# PCB-CMB-6_SKAARDUINO.net
KiCad netlist of a schematic drawn in EAGLE
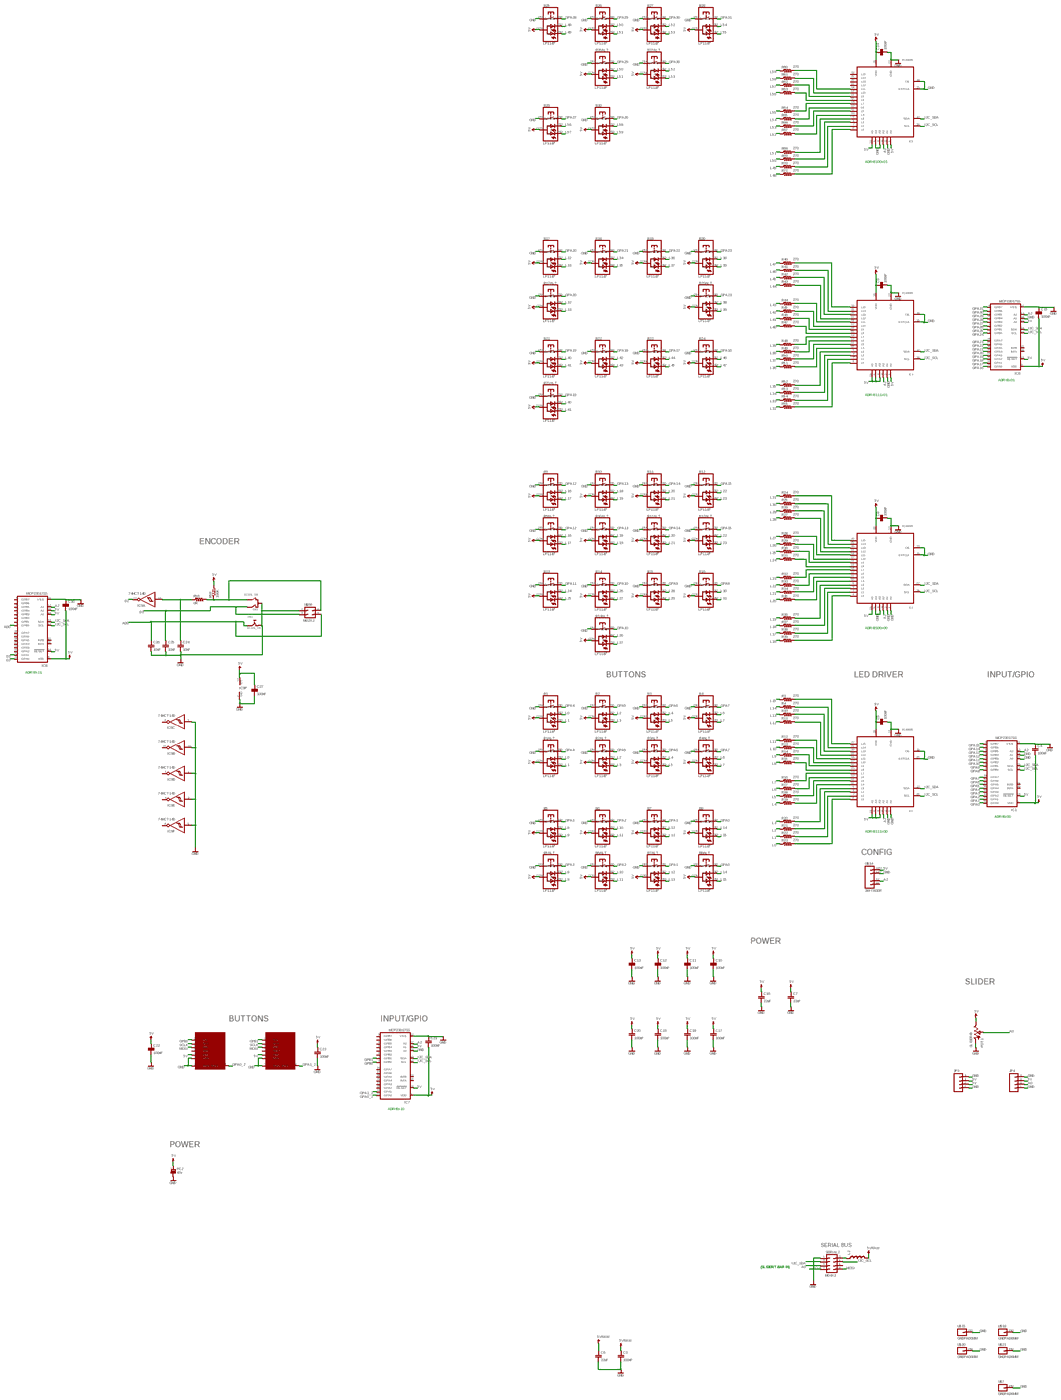
[diagram p0: schematic, sheet 1, overview]
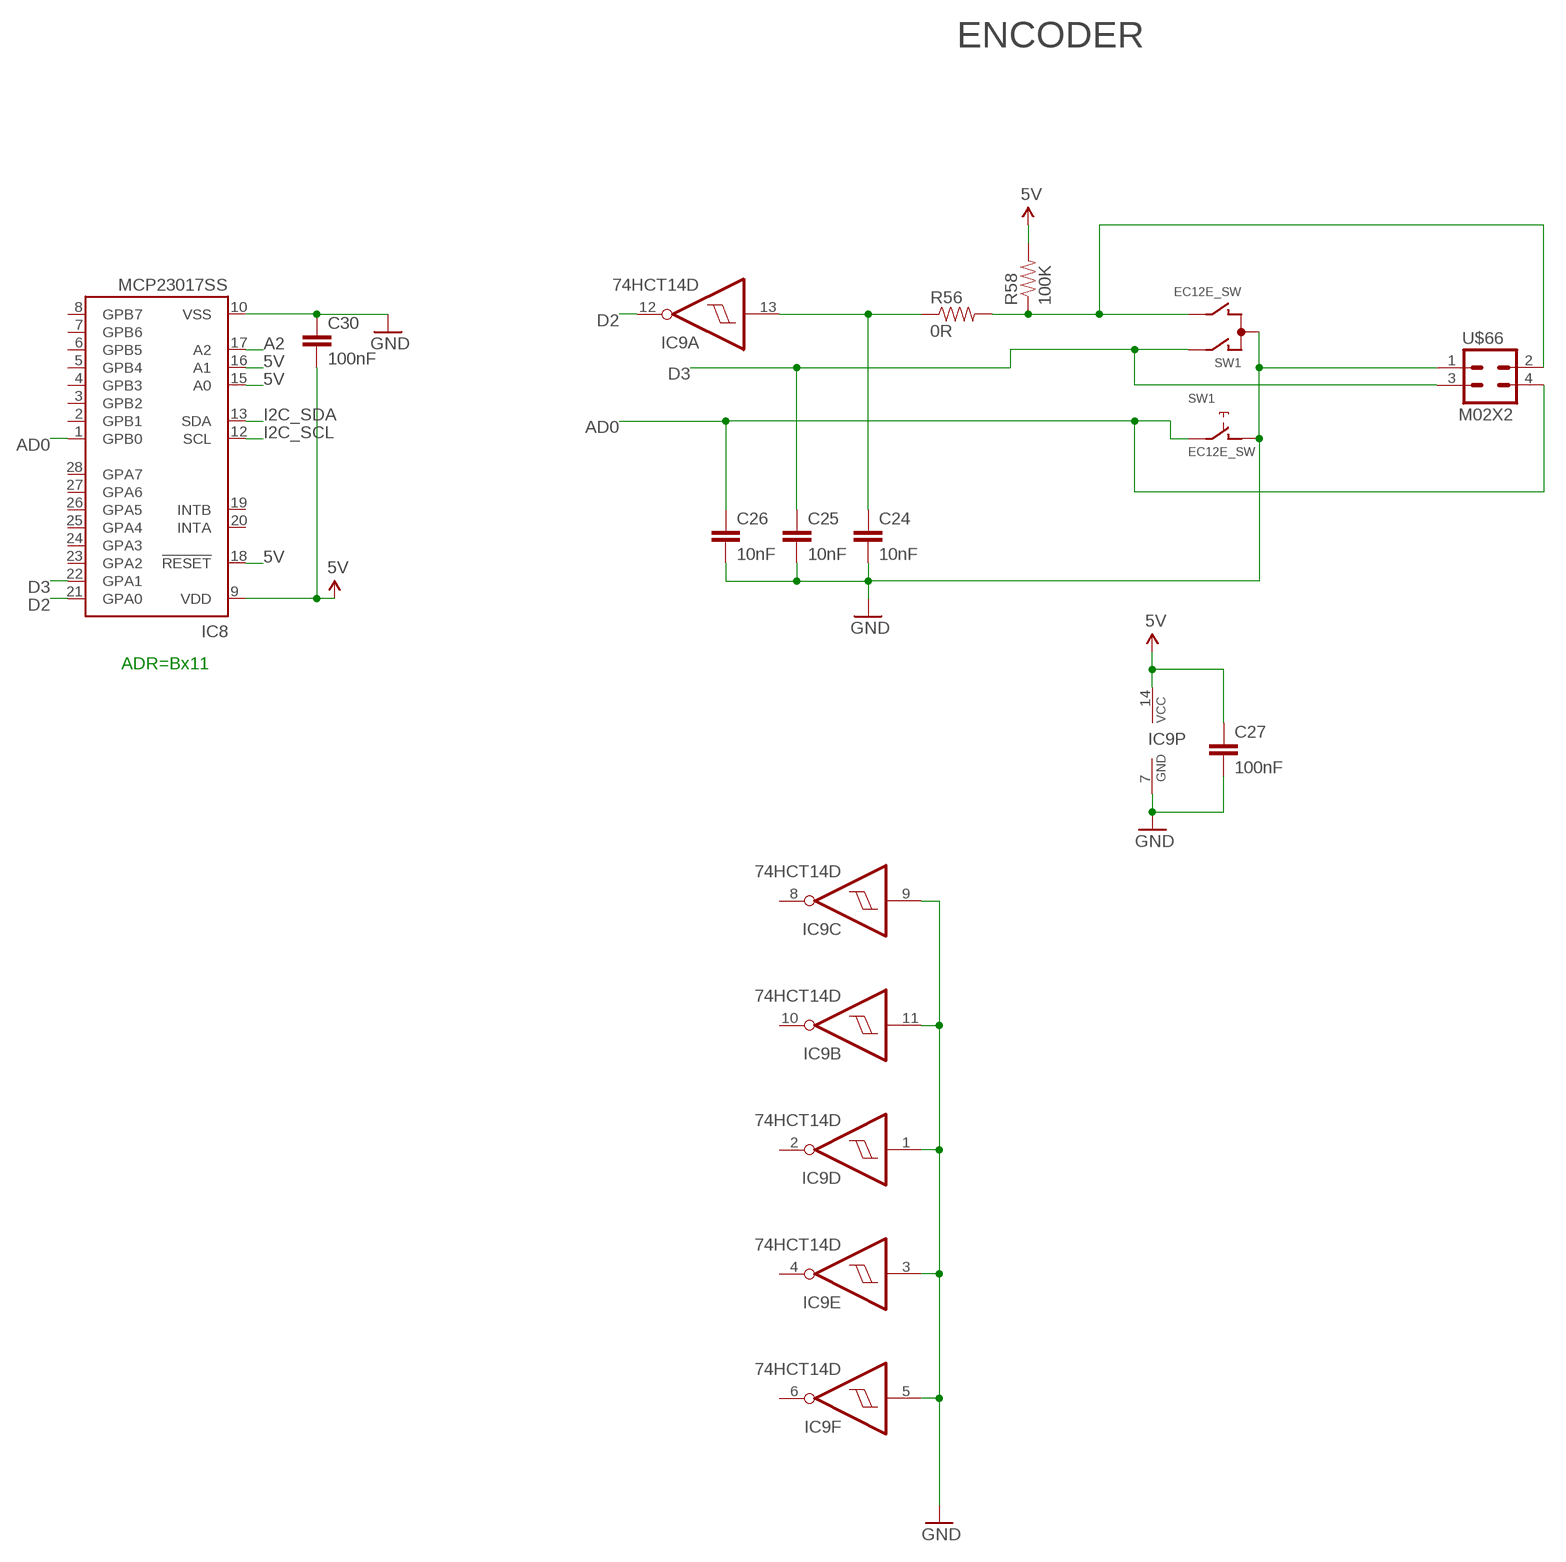
[diagram p1: schematic, sheet 1, part 1 of 5]
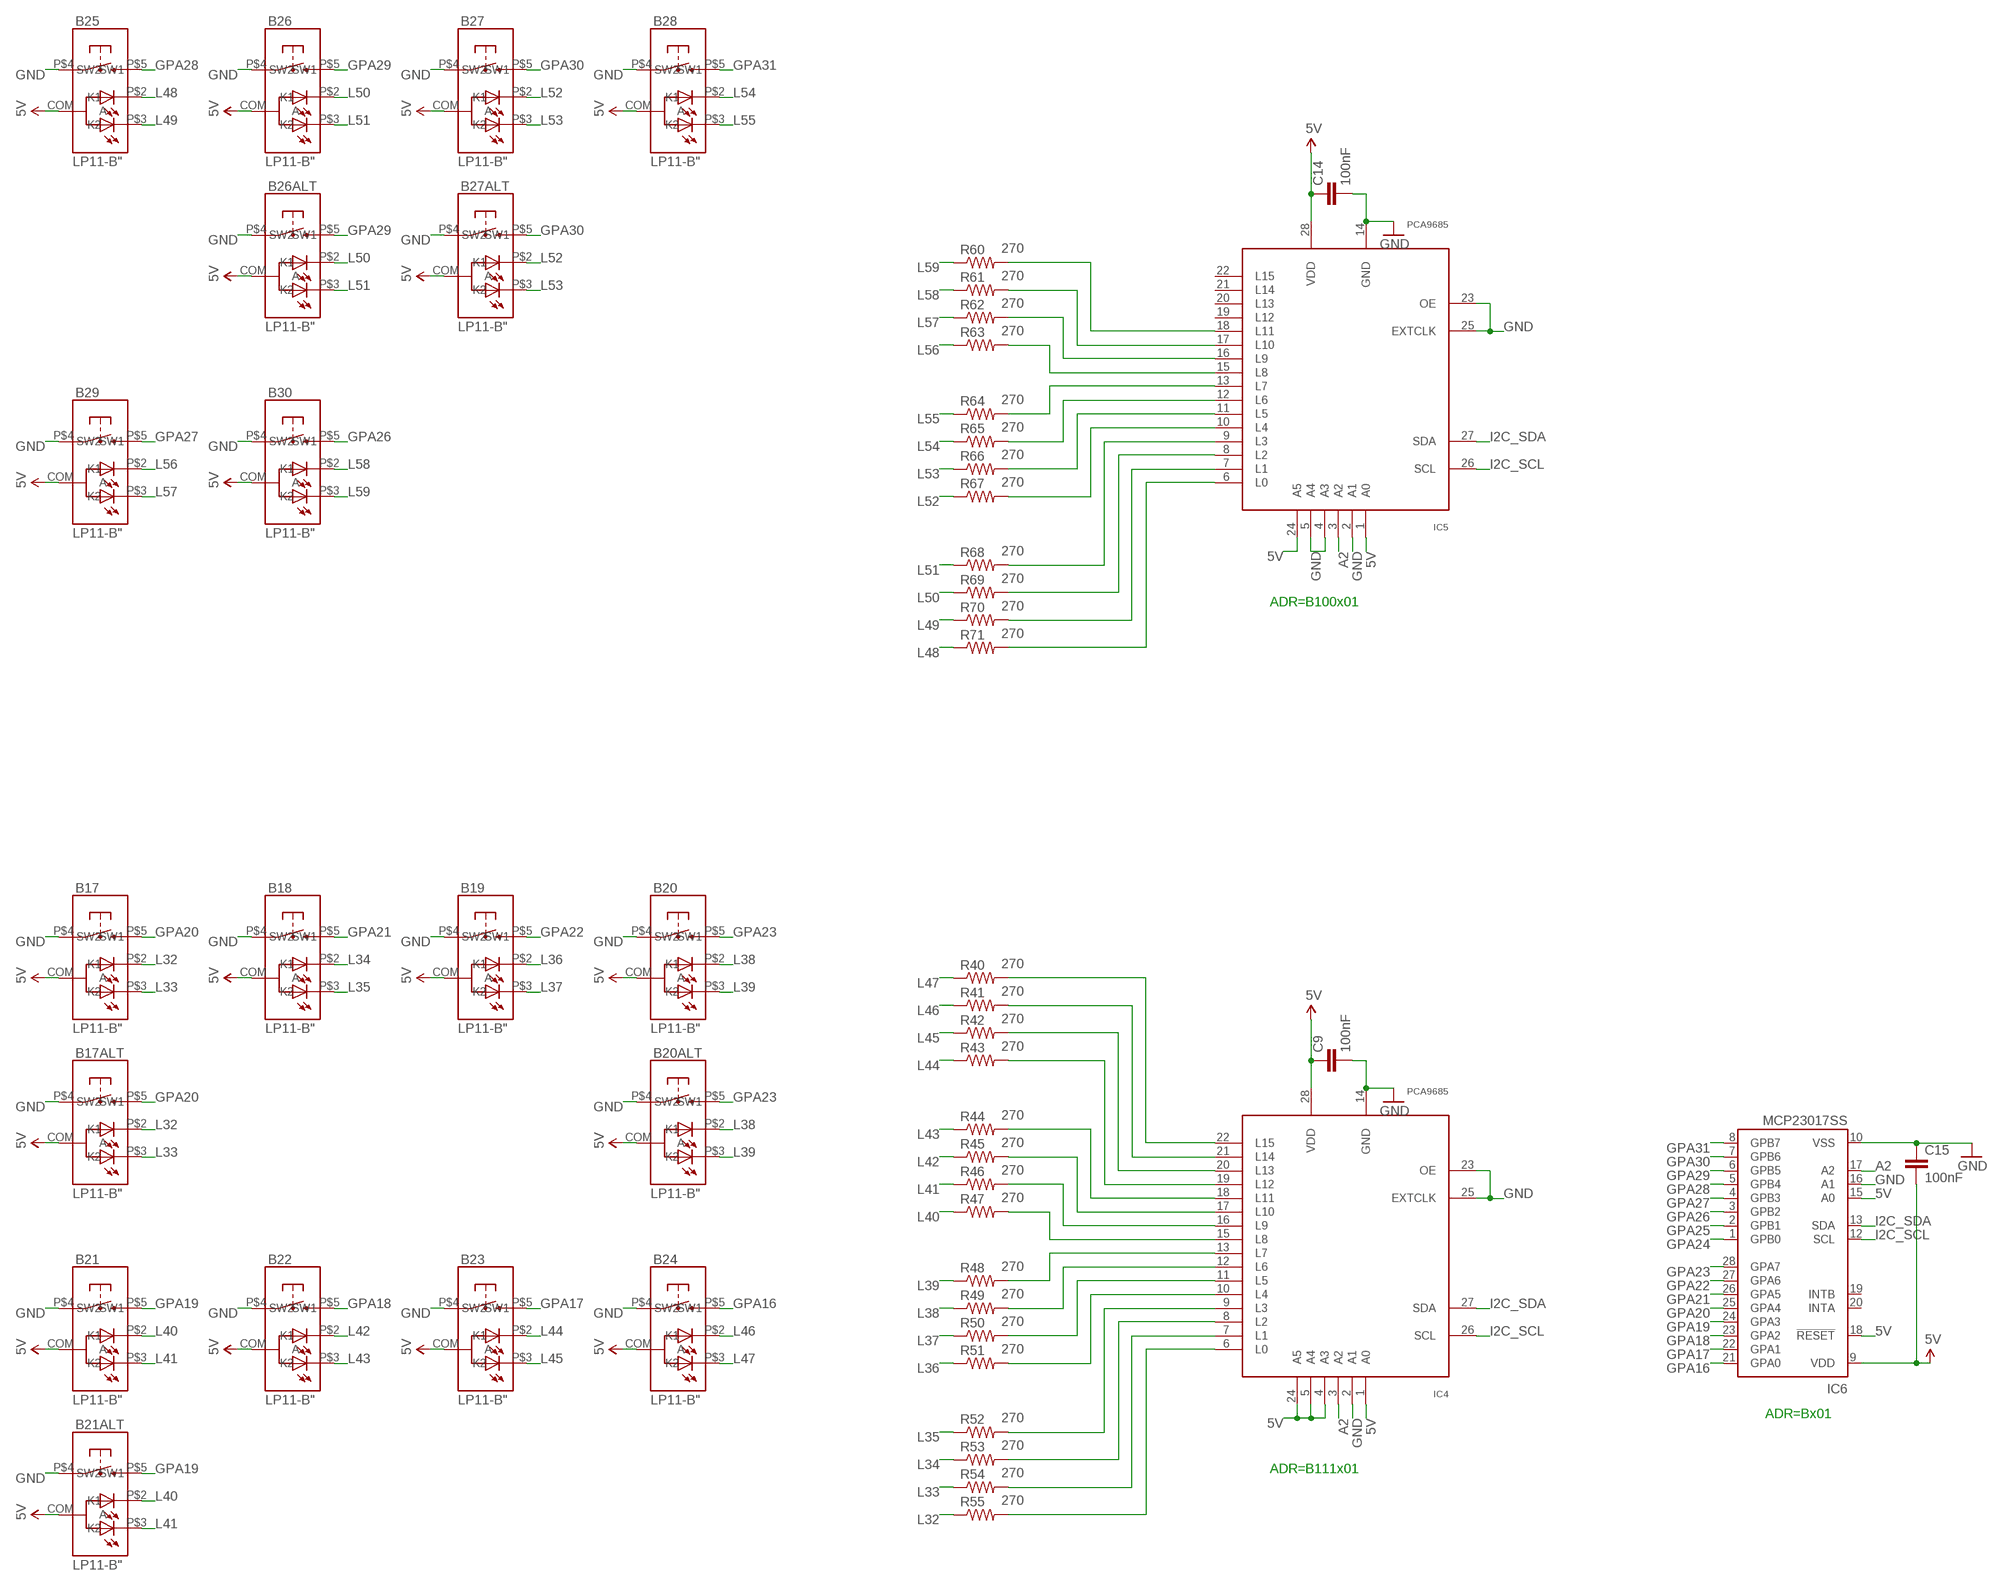
[diagram p2: schematic, sheet 1, part 2 of 5]
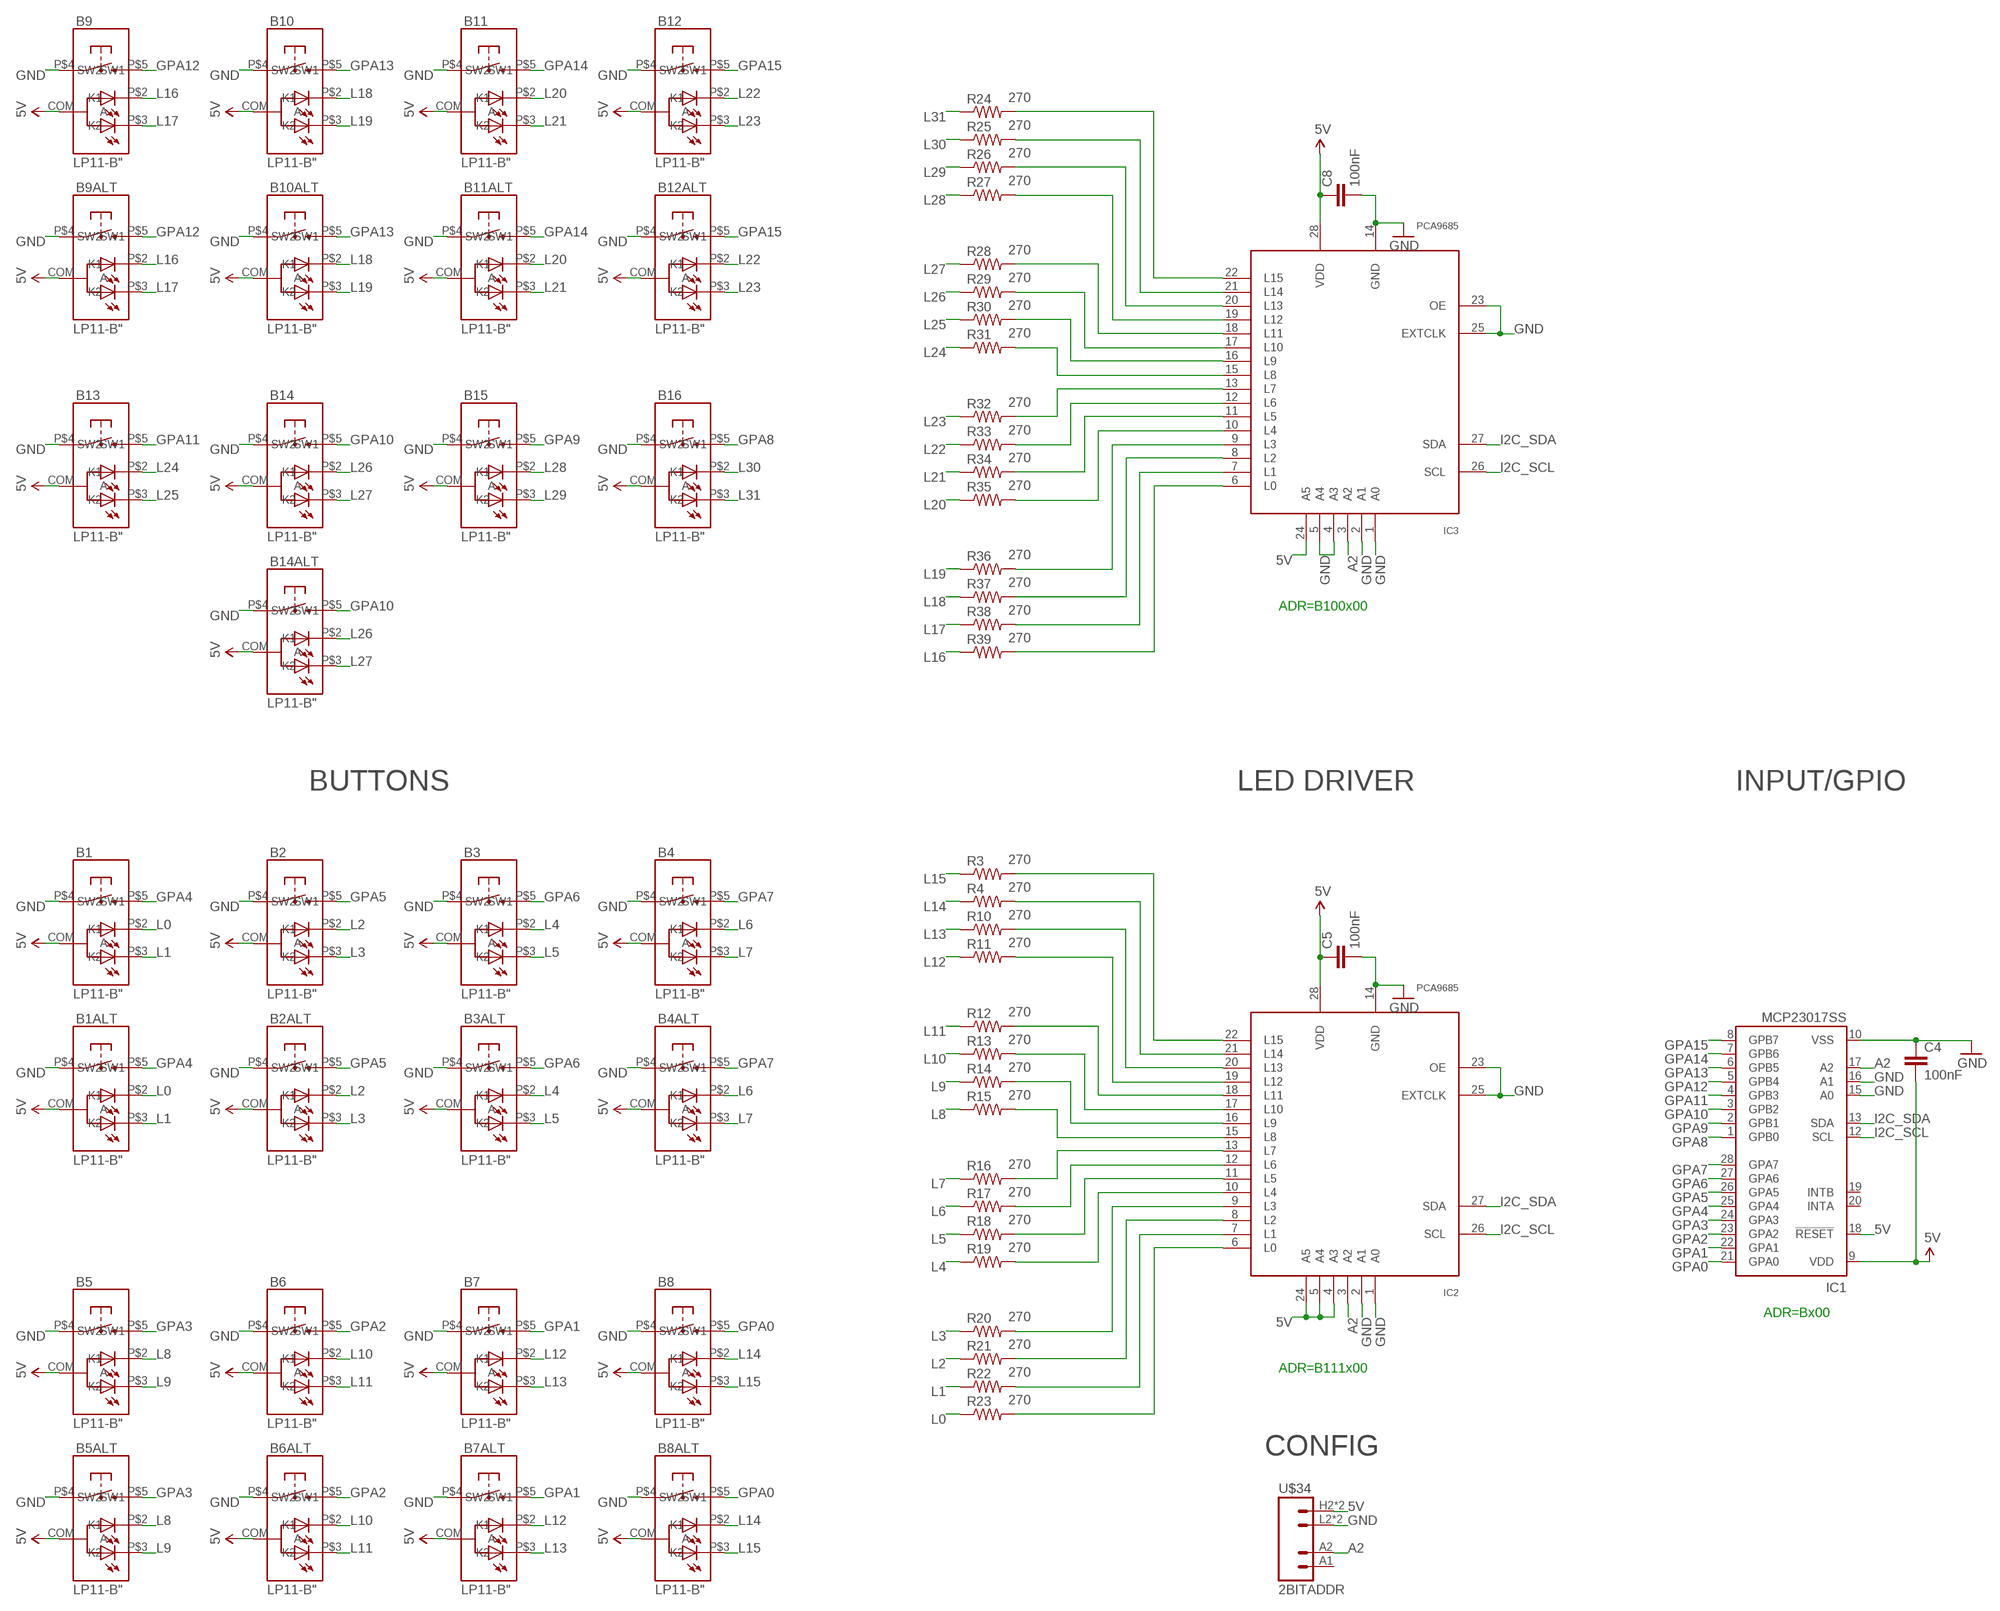
[diagram p3: schematic, sheet 1, part 3 of 5]
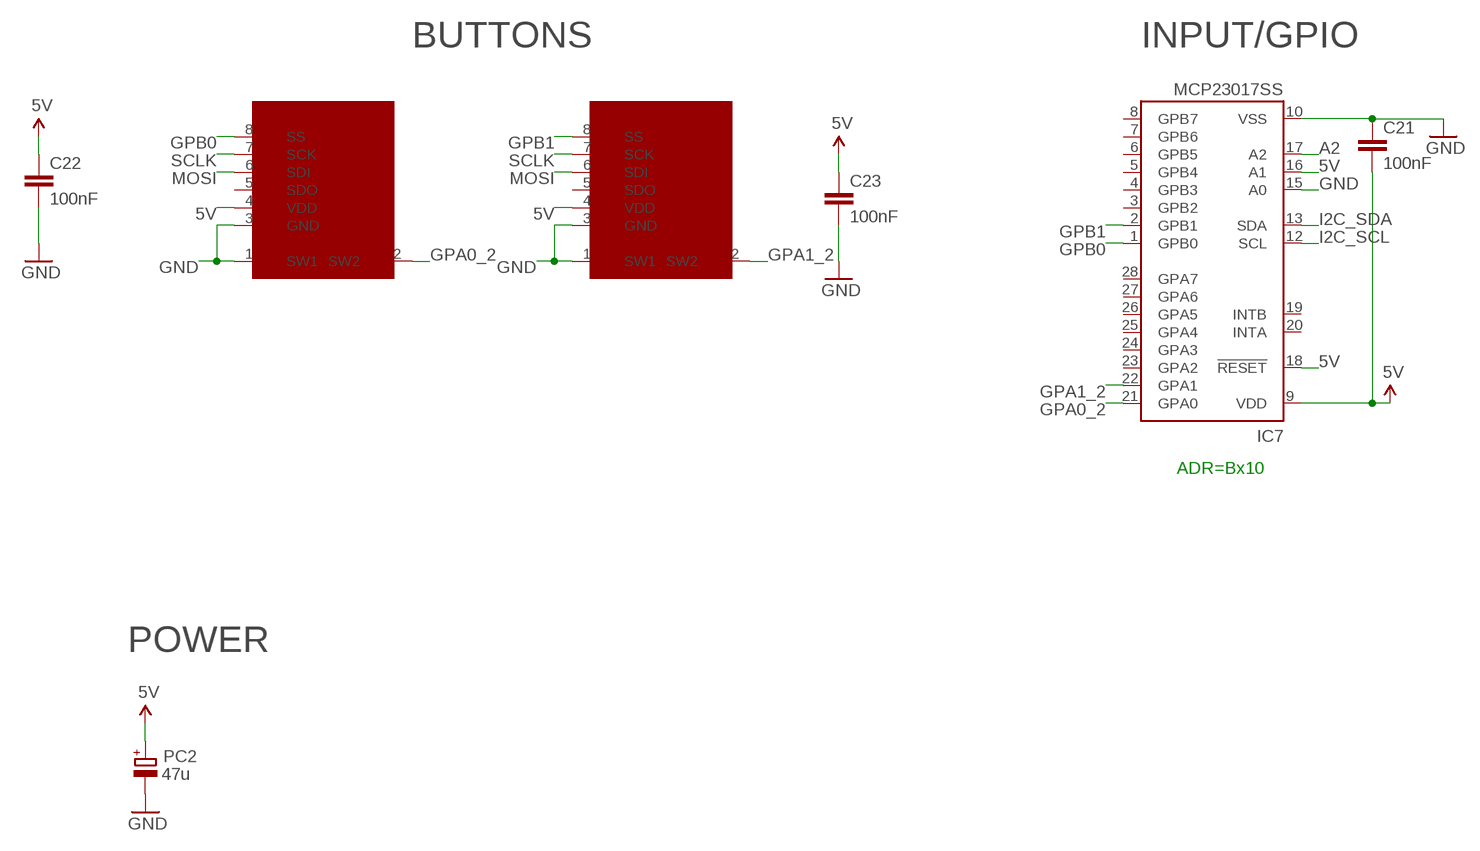
[diagram p4: schematic, sheet 1, part 4 of 5]
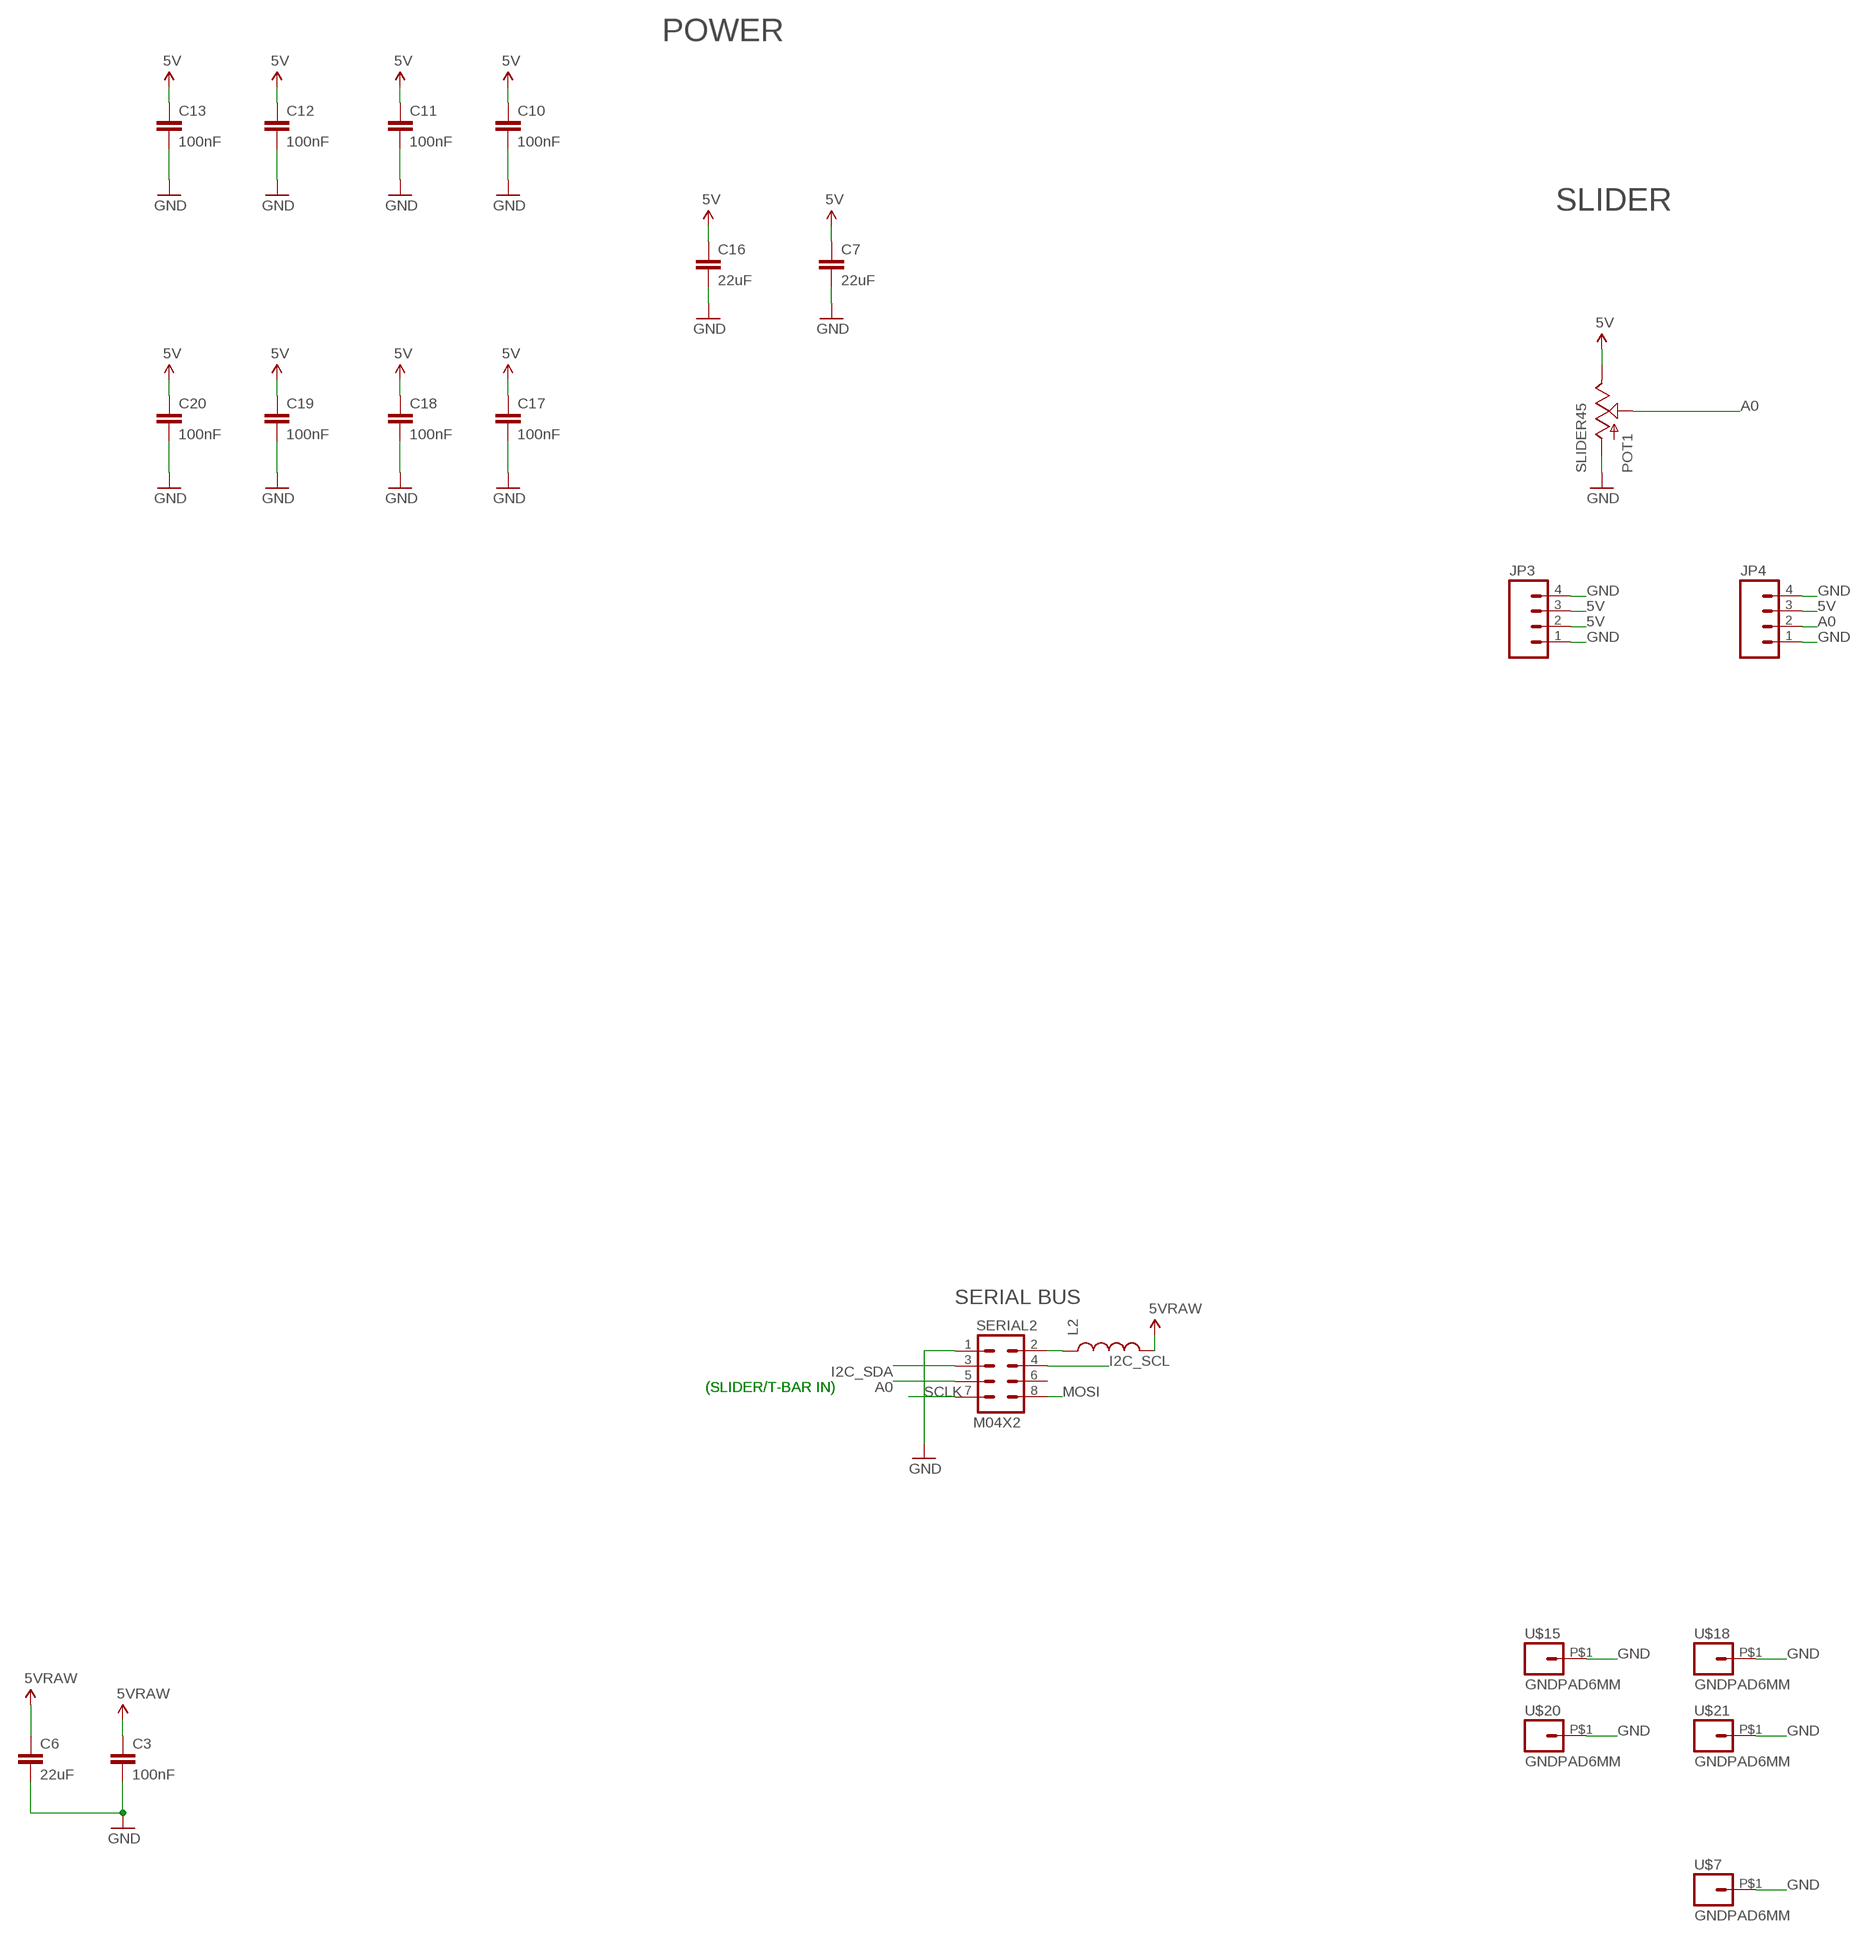
[diagram p5: schematic, sheet 1, part 5 of 5]

(export (version "E")
  (design (tool "Eeschema 10.0.6"))
  (components
    (comp (ref "B1")
      (value "LP11-B\"")
      (footprint "eagle-import:LP11")
      (libsource (lib "eagle-import") (part "LP11-B{dblquote}"))
    )
    (comp (ref "B1ALT")
      (value "LP11-B\"")
      (footprint "eagle-import:LP11")
      (libsource (lib "eagle-import") (part "LP11-B{dblquote}"))
    )
    (comp (ref "B2")
      (value "LP11-B\"")
      (footprint "eagle-import:LP11")
      (libsource (lib "eagle-import") (part "LP11-B{dblquote}"))
    )
    (comp (ref "B2ALT")
      (value "LP11-B\"")
      (footprint "eagle-import:LP11")
      (libsource (lib "eagle-import") (part "LP11-B{dblquote}"))
    )
    (comp (ref "B3")
      (value "LP11-B\"")
      (footprint "eagle-import:LP11")
      (libsource (lib "eagle-import") (part "LP11-B{dblquote}"))
    )
    (comp (ref "B3ALT")
      (value "LP11-B\"")
      (footprint "eagle-import:LP11")
      (libsource (lib "eagle-import") (part "LP11-B{dblquote}"))
    )
    (comp (ref "B4")
      (value "LP11-B\"")
      (footprint "eagle-import:LP11")
      (libsource (lib "eagle-import") (part "LP11-B{dblquote}"))
    )
    (comp (ref "B4ALT")
      (value "LP11-B\"")
      (footprint "eagle-import:LP11")
      (libsource (lib "eagle-import") (part "LP11-B{dblquote}"))
    )
    (comp (ref "B5")
      (value "LP11-B\"")
      (footprint "eagle-import:LP11")
      (libsource (lib "eagle-import") (part "LP11-B{dblquote}"))
    )
    (comp (ref "B5ALT")
      (value "LP11-B\"")
      (footprint "eagle-import:LP11")
      (libsource (lib "eagle-import") (part "LP11-B{dblquote}"))
    )
    (comp (ref "B6")
      (value "LP11-B\"")
      (footprint "eagle-import:LP11")
      (libsource (lib "eagle-import") (part "LP11-B{dblquote}"))
    )
    (comp (ref "B6ALT")
      (value "LP11-B\"")
      (footprint "eagle-import:LP11")
      (libsource (lib "eagle-import") (part "LP11-B{dblquote}"))
    )
    (comp (ref "B7")
      (value "LP11-B\"")
      (footprint "eagle-import:LP11")
      (libsource (lib "eagle-import") (part "LP11-B{dblquote}"))
    )
    (comp (ref "B7ALT")
      (value "LP11-B\"")
      (footprint "eagle-import:LP11")
      (libsource (lib "eagle-import") (part "LP11-B{dblquote}"))
    )
    (comp (ref "B8")
      (value "LP11-B\"")
      (footprint "eagle-import:LP11")
      (libsource (lib "eagle-import") (part "LP11-B{dblquote}"))
    )
    (comp (ref "B8ALT")
      (value "LP11-B\"")
      (footprint "eagle-import:LP11")
      (libsource (lib "eagle-import") (part "LP11-B{dblquote}"))
    )
    (comp (ref "B9")
      (value "LP11-B\"")
      (footprint "eagle-import:LP11")
      (libsource (lib "eagle-import") (part "LP11-B{dblquote}"))
    )
    (comp (ref "B9ALT")
      (value "LP11-B\"")
      (footprint "eagle-import:LP11")
      (libsource (lib "eagle-import") (part "LP11-B{dblquote}"))
    )
    (comp (ref "B10")
      (value "LP11-B\"")
      (footprint "eagle-import:LP11")
      (libsource (lib "eagle-import") (part "LP11-B{dblquote}"))
    )
    (comp (ref "B10ALT")
      (value "LP11-B\"")
      (footprint "eagle-import:LP11")
      (libsource (lib "eagle-import") (part "LP11-B{dblquote}"))
    )
    (comp (ref "B11")
      (value "LP11-B\"")
      (footprint "eagle-import:LP11")
      (libsource (lib "eagle-import") (part "LP11-B{dblquote}"))
    )
    (comp (ref "B11ALT")
      (value "LP11-B\"")
      (footprint "eagle-import:LP11")
      (libsource (lib "eagle-import") (part "LP11-B{dblquote}"))
    )
    (comp (ref "B12")
      (value "LP11-B\"")
      (footprint "eagle-import:LP11")
      (libsource (lib "eagle-import") (part "LP11-B{dblquote}"))
    )
    (comp (ref "B12ALT")
      (value "LP11-B\"")
      (footprint "eagle-import:LP11")
      (libsource (lib "eagle-import") (part "LP11-B{dblquote}"))
    )
    (comp (ref "B13")
      (value "LP11-B\"")
      (footprint "eagle-import:LP11")
      (libsource (lib "eagle-import") (part "LP11-B{dblquote}"))
    )
    (comp (ref "B14")
      (value "LP11-B\"")
      (footprint "eagle-import:LP11")
      (libsource (lib "eagle-import") (part "LP11-B{dblquote}"))
    )
    (comp (ref "B14ALT")
      (value "LP11-B\"")
      (footprint "eagle-import:LP11")
      (libsource (lib "eagle-import") (part "LP11-B{dblquote}"))
    )
    (comp (ref "B15")
      (value "LP11-B\"")
      (footprint "eagle-import:LP11")
      (libsource (lib "eagle-import") (part "LP11-B{dblquote}"))
    )
    (comp (ref "B16")
      (value "LP11-B\"")
      (footprint "eagle-import:LP11")
      (libsource (lib "eagle-import") (part "LP11-B{dblquote}"))
    )
    (comp (ref "B17")
      (value "LP11-B\"")
      (footprint "eagle-import:LP11")
      (libsource (lib "eagle-import") (part "LP11-B{dblquote}"))
    )
    (comp (ref "B17ALT")
      (value "LP11-B\"")
      (footprint "eagle-import:LP11")
      (libsource (lib "eagle-import") (part "LP11-B{dblquote}"))
    )
    (comp (ref "B18")
      (value "LP11-B\"")
      (footprint "eagle-import:LP11")
      (libsource (lib "eagle-import") (part "LP11-B{dblquote}"))
    )
    (comp (ref "B19")
      (value "LP11-B\"")
      (footprint "eagle-import:LP11")
      (libsource (lib "eagle-import") (part "LP11-B{dblquote}"))
    )
    (comp (ref "B20")
      (value "LP11-B\"")
      (footprint "eagle-import:LP11")
      (libsource (lib "eagle-import") (part "LP11-B{dblquote}"))
    )
    (comp (ref "B20ALT")
      (value "LP11-B\"")
      (footprint "eagle-import:LP11")
      (libsource (lib "eagle-import") (part "LP11-B{dblquote}"))
    )
    (comp (ref "B21")
      (value "LP11-B\"")
      (footprint "eagle-import:LP11")
      (libsource (lib "eagle-import") (part "LP11-B{dblquote}"))
    )
    (comp (ref "B21ALT")
      (value "LP11-B\"")
      (footprint "eagle-import:LP11")
      (libsource (lib "eagle-import") (part "LP11-B{dblquote}"))
    )
    (comp (ref "B22")
      (value "LP11-B\"")
      (footprint "eagle-import:LP11")
      (libsource (lib "eagle-import") (part "LP11-B{dblquote}"))
    )
    (comp (ref "B23")
      (value "LP11-B\"")
      (footprint "eagle-import:LP11")
      (libsource (lib "eagle-import") (part "LP11-B{dblquote}"))
    )
    (comp (ref "B24")
      (value "LP11-B\"")
      (footprint "eagle-import:LP11")
      (libsource (lib "eagle-import") (part "LP11-B{dblquote}"))
    )
    (comp (ref "B25")
      (value "LP11-B\"")
      (footprint "eagle-import:LP11")
      (libsource (lib "eagle-import") (part "LP11-B{dblquote}"))
    )
    (comp (ref "B26")
      (value "LP11-B\"")
      (footprint "eagle-import:LP11")
      (libsource (lib "eagle-import") (part "LP11-B{dblquote}"))
    )
    (comp (ref "B26ALT")
      (value "LP11-B\"")
      (footprint "eagle-import:LP11")
      (libsource (lib "eagle-import") (part "LP11-B{dblquote}"))
    )
    (comp (ref "B27")
      (value "LP11-B\"")
      (footprint "eagle-import:LP11")
      (libsource (lib "eagle-import") (part "LP11-B{dblquote}"))
    )
    (comp (ref "B27ALT")
      (value "LP11-B\"")
      (footprint "eagle-import:LP11")
      (libsource (lib "eagle-import") (part "LP11-B{dblquote}"))
    )
    (comp (ref "B28")
      (value "LP11-B\"")
      (footprint "eagle-import:LP11")
      (libsource (lib "eagle-import") (part "LP11-B{dblquote}"))
    )
    (comp (ref "B29")
      (value "LP11-B\"")
      (footprint "eagle-import:LP11")
      (libsource (lib "eagle-import") (part "LP11-B{dblquote}"))
    )
    (comp (ref "B30")
      (value "LP11-B\"")
      (footprint "eagle-import:LP11")
      (libsource (lib "eagle-import") (part "LP11-B{dblquote}"))
    )
    (comp (ref "C3")
      (value "100nF")
      (footprint "eagle-import:0603-CAP")
      (libsource (lib "eagle-import") (part "CAP0603-CAP"))
    )
    (comp (ref "C4")
      (value "100nF")
      (footprint "eagle-import:0603-CAP")
      (libsource (lib "eagle-import") (part "CAP0603-CAP"))
    )
    (comp (ref "C5")
      (value "100nF")
      (footprint "eagle-import:0603-CAP")
      (libsource (lib "eagle-import") (part "CAP0603-CAP"))
    )
    (comp (ref "C6")
      (value "22uF")
      (footprint "eagle-import:0805")
      (libsource (lib "eagle-import") (part "CAP0805"))
    )
    (comp (ref "C7")
      (value "22uF")
      (footprint "eagle-import:0805")
      (libsource (lib "eagle-import") (part "CAP0805"))
    )
    (comp (ref "C8")
      (value "100nF")
      (footprint "eagle-import:0603-CAP")
      (libsource (lib "eagle-import") (part "CAP0603-CAP"))
    )
    (comp (ref "C9")
      (value "100nF")
      (footprint "eagle-import:0603-CAP")
      (libsource (lib "eagle-import") (part "CAP0603-CAP"))
    )
    (comp (ref "C10")
      (value "100nF")
      (footprint "eagle-import:0603-CAP")
      (libsource (lib "eagle-import") (part "CAP0603-CAP"))
    )
    (comp (ref "C11")
      (value "100nF")
      (footprint "eagle-import:0603-CAP")
      (libsource (lib "eagle-import") (part "CAP0603-CAP"))
    )
    (comp (ref "C12")
      (value "100nF")
      (footprint "eagle-import:0603-CAP")
      (libsource (lib "eagle-import") (part "CAP0603-CAP"))
    )
    (comp (ref "C13")
      (value "100nF")
      (footprint "eagle-import:0603-CAP")
      (libsource (lib "eagle-import") (part "CAP0603-CAP"))
    )
    (comp (ref "C14")
      (value "100nF")
      (footprint "eagle-import:0603-CAP")
      (libsource (lib "eagle-import") (part "CAP0603-CAP"))
    )
    (comp (ref "C15")
      (value "100nF")
      (footprint "eagle-import:0603-CAP")
      (libsource (lib "eagle-import") (part "CAP0603-CAP"))
    )
    (comp (ref "C16")
      (value "22uF")
      (footprint "eagle-import:0805")
      (libsource (lib "eagle-import") (part "CAP0805"))
    )
    (comp (ref "C17")
      (value "100nF")
      (footprint "eagle-import:0603-CAP")
      (libsource (lib "eagle-import") (part "CAP0603-CAP"))
    )
    (comp (ref "C18")
      (value "100nF")
      (footprint "eagle-import:0603-CAP")
      (libsource (lib "eagle-import") (part "CAP0603-CAP"))
    )
    (comp (ref "C19")
      (value "100nF")
      (footprint "eagle-import:0603-CAP")
      (libsource (lib "eagle-import") (part "CAP0603-CAP"))
    )
    (comp (ref "C20")
      (value "100nF")
      (footprint "eagle-import:0603-CAP")
      (libsource (lib "eagle-import") (part "CAP0603-CAP"))
    )
    (comp (ref "C21")
      (value "100nF")
      (footprint "eagle-import:0603-CAP")
      (libsource (lib "eagle-import") (part "CAP0603-CAP"))
    )
    (comp (ref "C22")
      (value "100nF")
      (footprint "eagle-import:0603-CAP")
      (libsource (lib "eagle-import") (part "CAP0603-CAP"))
    )
    (comp (ref "C23")
      (value "100nF")
      (footprint "eagle-import:0603-CAP")
      (libsource (lib "eagle-import") (part "CAP0603-CAP"))
    )
    (comp (ref "C24")
      (value "10nF")
      (footprint "eagle-import:0603-CAP")
      (libsource (lib "eagle-import") (part "CAP0603-CAP"))
    )
    (comp (ref "C25")
      (value "10nF")
      (footprint "eagle-import:0603-CAP")
      (libsource (lib "eagle-import") (part "CAP0603-CAP"))
    )
    (comp (ref "C26")
      (value "10nF")
      (footprint "eagle-import:0603-CAP")
      (libsource (lib "eagle-import") (part "CAP0603-CAP"))
    )
    (comp (ref "C27")
      (value "100nF")
      (footprint "eagle-import:0603-CAP")
      (libsource (lib "eagle-import") (part "CAP0603-CAP"))
    )
    (comp (ref "C30")
      (value "100nF")
      (footprint "eagle-import:0603-CAP")
      (libsource (lib "eagle-import") (part "CAP0603-CAP"))
    )
    (comp (ref "IC1")
      (value "MCP23017SS")
      (footprint "eagle-import:SSOP28")
      (fields
        (field (name "MF") "MICROCHIP")
        (field (name "MPN") "MCP23017-E/SS")
        (field (name "MPN_1") "MCP23017-E/SS")
        (field (name "OC_FARNELL") "1467674")
        (field (name "OC_NEWARK") "31K2960")
      )
      (libsource (lib "eagle-import") (part "MCP23017SS"))
    )
    (comp (ref "IC2")
      (value "PCA9685")
      (footprint "eagle-import:TSSOP28")
      (libsource (lib "eagle-import") (part "PCA9685"))
    )
    (comp (ref "IC3")
      (value "PCA9685")
      (footprint "eagle-import:TSSOP28")
      (libsource (lib "eagle-import") (part "PCA9685"))
    )
    (comp (ref "IC4")
      (value "PCA9685")
      (footprint "eagle-import:TSSOP28")
      (libsource (lib "eagle-import") (part "PCA9685"))
    )
    (comp (ref "IC5")
      (value "PCA9685")
      (footprint "eagle-import:TSSOP28")
      (libsource (lib "eagle-import") (part "PCA9685"))
    )
    (comp (ref "IC6")
      (value "MCP23017SS")
      (footprint "eagle-import:SSOP28")
      (fields
        (field (name "MF") "MICROCHIP")
        (field (name "MPN") "MCP23017-E/SS")
        (field (name "MPN_1") "MCP23017-E/SS")
        (field (name "OC_FARNELL") "1467674")
        (field (name "OC_NEWARK") "31K2960")
      )
      (libsource (lib "eagle-import") (part "MCP23017SS"))
    )
    (comp (ref "IC7")
      (value "MCP23017SS")
      (footprint "eagle-import:SSOP28")
      (fields
        (field (name "MF") "MICROCHIP")
        (field (name "MPN") "MCP23017-E/SS")
        (field (name "MPN_1") "MCP23017-E/SS")
        (field (name "OC_FARNELL") "1467674")
        (field (name "OC_NEWARK") "31K2960")
      )
      (libsource (lib "eagle-import") (part "MCP23017SS"))
    )
    (comp (ref "IC8")
      (value "MCP23017SS")
      (footprint "eagle-import:SSOP28")
      (fields
        (field (name "MF") "MICROCHIP")
        (field (name "MPN") "MCP23017-E/SS")
        (field (name "MPN_1") "MCP23017-E/SS")
        (field (name "OC_FARNELL") "1467674")
        (field (name "OC_NEWARK") "31K2960")
      )
      (libsource (lib "eagle-import") (part "MCP23017SS"))
    )
    (comp (ref "IC9")
      (value "74HCT14D")
      (footprint "eagle-import:SO14")
      (libsource (lib "eagle-import") (part "7414DHCT"))
    )
    (comp (ref "JP3")
      (value "M04PTH")
      (footprint "eagle-import:1X04")
      (libsource (lib "eagle-import") (part "M04PTH"))
    )
    (comp (ref "JP4")
      (value "M04PTH")
      (footprint "eagle-import:1X04")
      (libsource (lib "eagle-import") (part "M04PTH"))
    )
    (comp (ref "L2")
      (value "INDUCTOR0805")
      (footprint "eagle-import:0805")
      (libsource (lib "eagle-import") (part "INDUCTOR0805"))
    )
    (comp (ref "PC2")
      (value "47u")
      (footprint "eagle-import:PANASONIC_D")
      (libsource (lib "eagle-import") (part "CPOL-EUD"))
    )
    (comp (ref "POT1")
      (value "SLIDER45")
      (footprint "eagle-import:SLIDER45")
      (libsource (lib "eagle-import") (part "SLIDER45"))
    )
    (comp (ref "R3")
      (value "270")
      (footprint "eagle-import:0603-RES")
      (libsource (lib "eagle-import") (part "RESISTOR0603-RES"))
    )
    (comp (ref "R4")
      (value "270")
      (footprint "eagle-import:0603-RES")
      (libsource (lib "eagle-import") (part "RESISTOR0603-RES"))
    )
    (comp (ref "R10")
      (value "270")
      (footprint "eagle-import:0603-RES")
      (libsource (lib "eagle-import") (part "RESISTOR0603-RES"))
    )
    (comp (ref "R11")
      (value "270")
      (footprint "eagle-import:0603-RES")
      (libsource (lib "eagle-import") (part "RESISTOR0603-RES"))
    )
    (comp (ref "R12")
      (value "270")
      (footprint "eagle-import:0603-RES")
      (libsource (lib "eagle-import") (part "RESISTOR0603-RES"))
    )
    (comp (ref "R13")
      (value "270")
      (footprint "eagle-import:0603-RES")
      (libsource (lib "eagle-import") (part "RESISTOR0603-RES"))
    )
    (comp (ref "R14")
      (value "270")
      (footprint "eagle-import:0603-RES")
      (libsource (lib "eagle-import") (part "RESISTOR0603-RES"))
    )
    (comp (ref "R15")
      (value "270")
      (footprint "eagle-import:0603-RES")
      (libsource (lib "eagle-import") (part "RESISTOR0603-RES"))
    )
    (comp (ref "R16")
      (value "270")
      (footprint "eagle-import:0603-RES")
      (libsource (lib "eagle-import") (part "RESISTOR0603-RES"))
    )
    (comp (ref "R17")
      (value "270")
      (footprint "eagle-import:0603-RES")
      (libsource (lib "eagle-import") (part "RESISTOR0603-RES"))
    )
    (comp (ref "R18")
      (value "270")
      (footprint "eagle-import:0603-RES")
      (libsource (lib "eagle-import") (part "RESISTOR0603-RES"))
    )
    (comp (ref "R19")
      (value "270")
      (footprint "eagle-import:0603-RES")
      (libsource (lib "eagle-import") (part "RESISTOR0603-RES"))
    )
    (comp (ref "R20")
      (value "270")
      (footprint "eagle-import:0603-RES")
      (libsource (lib "eagle-import") (part "RESISTOR0603-RES"))
    )
    (comp (ref "R21")
      (value "270")
      (footprint "eagle-import:0603-RES")
      (libsource (lib "eagle-import") (part "RESISTOR0603-RES"))
    )
    (comp (ref "R22")
      (value "270")
      (footprint "eagle-import:0603-RES")
      (libsource (lib "eagle-import") (part "RESISTOR0603-RES"))
    )
    (comp (ref "R23")
      (value "270")
      (footprint "eagle-import:0603-RES")
      (libsource (lib "eagle-import") (part "RESISTOR0603-RES"))
    )
    (comp (ref "R24")
      (value "270")
      (footprint "eagle-import:0603-RES")
      (libsource (lib "eagle-import") (part "RESISTOR0603-RES"))
    )
    (comp (ref "R25")
      (value "270")
      (footprint "eagle-import:0603-RES")
      (libsource (lib "eagle-import") (part "RESISTOR0603-RES"))
    )
    (comp (ref "R26")
      (value "270")
      (footprint "eagle-import:0603-RES")
      (libsource (lib "eagle-import") (part "RESISTOR0603-RES"))
    )
    (comp (ref "R27")
      (value "270")
      (footprint "eagle-import:0603-RES")
      (libsource (lib "eagle-import") (part "RESISTOR0603-RES"))
    )
    (comp (ref "R28")
      (value "270")
      (footprint "eagle-import:0603-RES")
      (libsource (lib "eagle-import") (part "RESISTOR0603-RES"))
    )
    (comp (ref "R29")
      (value "270")
      (footprint "eagle-import:0603-RES")
      (libsource (lib "eagle-import") (part "RESISTOR0603-RES"))
    )
    (comp (ref "R30")
      (value "270")
      (footprint "eagle-import:0603-RES")
      (libsource (lib "eagle-import") (part "RESISTOR0603-RES"))
    )
    (comp (ref "R31")
      (value "270")
      (footprint "eagle-import:0603-RES")
      (libsource (lib "eagle-import") (part "RESISTOR0603-RES"))
    )
    (comp (ref "R32")
      (value "270")
      (footprint "eagle-import:0603-RES")
      (libsource (lib "eagle-import") (part "RESISTOR0603-RES"))
    )
    (comp (ref "R33")
      (value "270")
      (footprint "eagle-import:0603-RES")
      (libsource (lib "eagle-import") (part "RESISTOR0603-RES"))
    )
    (comp (ref "R34")
      (value "270")
      (footprint "eagle-import:0603-RES")
      (libsource (lib "eagle-import") (part "RESISTOR0603-RES"))
    )
    (comp (ref "R35")
      (value "270")
      (footprint "eagle-import:0603-RES")
      (libsource (lib "eagle-import") (part "RESISTOR0603-RES"))
    )
    (comp (ref "R36")
      (value "270")
      (footprint "eagle-import:0603-RES")
      (libsource (lib "eagle-import") (part "RESISTOR0603-RES"))
    )
    (comp (ref "R37")
      (value "270")
      (footprint "eagle-import:0603-RES")
      (libsource (lib "eagle-import") (part "RESISTOR0603-RES"))
    )
    (comp (ref "R38")
      (value "270")
      (footprint "eagle-import:0603-RES")
      (libsource (lib "eagle-import") (part "RESISTOR0603-RES"))
    )
    (comp (ref "R39")
      (value "270")
      (footprint "eagle-import:0603-RES")
      (libsource (lib "eagle-import") (part "RESISTOR0603-RES"))
    )
    (comp (ref "R40")
      (value "270")
      (footprint "eagle-import:0603-RES")
      (libsource (lib "eagle-import") (part "RESISTOR0603-RES"))
    )
    (comp (ref "R41")
      (value "270")
      (footprint "eagle-import:0603-RES")
      (libsource (lib "eagle-import") (part "RESISTOR0603-RES"))
    )
    (comp (ref "R42")
      (value "270")
      (footprint "eagle-import:0603-RES")
      (libsource (lib "eagle-import") (part "RESISTOR0603-RES"))
    )
    (comp (ref "R43")
      (value "270")
      (footprint "eagle-import:0603-RES")
      (libsource (lib "eagle-import") (part "RESISTOR0603-RES"))
    )
    (comp (ref "R44")
      (value "270")
      (footprint "eagle-import:0603-RES")
      (libsource (lib "eagle-import") (part "RESISTOR0603-RES"))
    )
    (comp (ref "R45")
      (value "270")
      (footprint "eagle-import:0603-RES")
      (libsource (lib "eagle-import") (part "RESISTOR0603-RES"))
    )
    (comp (ref "R46")
      (value "270")
      (footprint "eagle-import:0603-RES")
      (libsource (lib "eagle-import") (part "RESISTOR0603-RES"))
    )
    (comp (ref "R47")
      (value "270")
      (footprint "eagle-import:0603-RES")
      (libsource (lib "eagle-import") (part "RESISTOR0603-RES"))
    )
    (comp (ref "R48")
      (value "270")
      (footprint "eagle-import:0603-RES")
      (libsource (lib "eagle-import") (part "RESISTOR0603-RES"))
    )
    (comp (ref "R49")
      (value "270")
      (footprint "eagle-import:0603-RES")
      (libsource (lib "eagle-import") (part "RESISTOR0603-RES"))
    )
    (comp (ref "R50")
      (value "270")
      (footprint "eagle-import:0603-RES")
      (libsource (lib "eagle-import") (part "RESISTOR0603-RES"))
    )
    (comp (ref "R51")
      (value "270")
      (footprint "eagle-import:0603-RES")
      (libsource (lib "eagle-import") (part "RESISTOR0603-RES"))
    )
    (comp (ref "R52")
      (value "270")
      (footprint "eagle-import:0603-RES")
      (libsource (lib "eagle-import") (part "RESISTOR0603-RES"))
    )
    (comp (ref "R53")
      (value "270")
      (footprint "eagle-import:0603-RES")
      (libsource (lib "eagle-import") (part "RESISTOR0603-RES"))
    )
    (comp (ref "R54")
      (value "270")
      (footprint "eagle-import:0603-RES")
      (libsource (lib "eagle-import") (part "RESISTOR0603-RES"))
    )
    (comp (ref "R55")
      (value "270")
      (footprint "eagle-import:0603-RES")
      (libsource (lib "eagle-import") (part "RESISTOR0603-RES"))
    )
    (comp (ref "R56")
      (value "0R")
      (footprint "eagle-import:0603-RES")
      (libsource (lib "eagle-import") (part "RESISTOR0603-RES"))
    )
    (comp (ref "R58")
      (value "100K")
      (footprint "eagle-import:0603-RES")
      (libsource (lib "eagle-import") (part "RESISTOR0603-RES"))
    )
    (comp (ref "R60")
      (value "270")
      (footprint "eagle-import:0603-RES")
      (libsource (lib "eagle-import") (part "RESISTOR0603-RES"))
    )
    (comp (ref "R61")
      (value "270")
      (footprint "eagle-import:0603-RES")
      (libsource (lib "eagle-import") (part "RESISTOR0603-RES"))
    )
    (comp (ref "R62")
      (value "270")
      (footprint "eagle-import:0603-RES")
      (libsource (lib "eagle-import") (part "RESISTOR0603-RES"))
    )
    (comp (ref "R63")
      (value "270")
      (footprint "eagle-import:0603-RES")
      (libsource (lib "eagle-import") (part "RESISTOR0603-RES"))
    )
    (comp (ref "R64")
      (value "270")
      (footprint "eagle-import:0603-RES")
      (libsource (lib "eagle-import") (part "RESISTOR0603-RES"))
    )
    (comp (ref "R65")
      (value "270")
      (footprint "eagle-import:0603-RES")
      (libsource (lib "eagle-import") (part "RESISTOR0603-RES"))
    )
    (comp (ref "R66")
      (value "270")
      (footprint "eagle-import:0603-RES")
      (libsource (lib "eagle-import") (part "RESISTOR0603-RES"))
    )
    (comp (ref "R67")
      (value "270")
      (footprint "eagle-import:0603-RES")
      (libsource (lib "eagle-import") (part "RESISTOR0603-RES"))
    )
    (comp (ref "R68")
      (value "270")
      (footprint "eagle-import:0603-RES")
      (libsource (lib "eagle-import") (part "RESISTOR0603-RES"))
    )
    (comp (ref "R69")
      (value "270")
      (footprint "eagle-import:0603-RES")
      (libsource (lib "eagle-import") (part "RESISTOR0603-RES"))
    )
    (comp (ref "R70")
      (value "270")
      (footprint "eagle-import:0603-RES")
      (libsource (lib "eagle-import") (part "RESISTOR0603-RES"))
    )
    (comp (ref "R71")
      (value "270")
      (footprint "eagle-import:0603-RES")
      (libsource (lib "eagle-import") (part "RESISTOR0603-RES"))
    )
    (comp (ref "SERIAL2")
      (value "M04X2")
      (footprint "eagle-import:2X4")
      (libsource (lib "eagle-import") (part "M04X2"))
    )
    (comp (ref "SSW1")
      (value "SMART_SWITCHSMART_SWITCH_8PIN")
      (footprint "eagle-import:SMART_SWITCH")
      (libsource (lib "eagle-import") (part "SMART_SWITCHSMART_SWITCH_8PIN"))
    )
    (comp (ref "SSW2")
      (value "SMART_SWITCHSMART_SWITCH_8PIN")
      (footprint "eagle-import:SMART_SWITCH")
      (libsource (lib "eagle-import") (part "SMART_SWITCHSMART_SWITCH_8PIN"))
    )
    (comp (ref "SW1")
      (value "EC12E_SW")
      (footprint "eagle-import:ALPS_EC12E_SW")
      (fields (field (name "MPN") "EC12E2424407"))
      (libsource (lib "eagle-import") (part "EC12E_SW"))
    )
    (comp (ref "U$7")
      (value "GNDPAD6MM")
      (footprint "eagle-import:3.2MMPAD6MM")
      (libsource (lib "eagle-import") (part "GNDPAD6MM"))
    )
    (comp (ref "U$15")
      (value "GNDPAD6MM")
      (footprint "eagle-import:3.2MMPAD6MM")
      (libsource (lib "eagle-import") (part "GNDPAD6MM"))
    )
    (comp (ref "U$18")
      (value "GNDPAD6MM")
      (footprint "eagle-import:3.2MMPAD6MM")
      (libsource (lib "eagle-import") (part "GNDPAD6MM"))
    )
    (comp (ref "U$20")
      (value "GNDPAD6MM")
      (footprint "eagle-import:3.2MMPAD6MM")
      (libsource (lib "eagle-import") (part "GNDPAD6MM"))
    )
    (comp (ref "U$21")
      (value "GNDPAD6MM")
      (footprint "eagle-import:3.2MMPAD6MM")
      (libsource (lib "eagle-import") (part "GNDPAD6MM"))
    )
    (comp (ref "U$34")
      (value "2BITADDR")
      (footprint "eagle-import:2BITADDR")
      (libsource (lib "eagle-import") (part "2BITADDR"))
    )
    (comp (ref "U$66")
      (value "M02X2")
      (footprint "eagle-import:2X2")
      (libsource (lib "eagle-import") (part "M02X2"))
    )
  )
  (nets
    (net (code "1") (name "5V") (class "Default")
      (node (ref "B1") (pin "COM") (pinfunction "A_COM") (pintype "bidirectional"))
      (node (ref "B10") (pin "COM") (pinfunction "A_COM") (pintype "bidirectional"))
      (node (ref "B10ALT") (pin "COM") (pinfunction "A_COM") (pintype "bidirectional"))
      (node (ref "B11") (pin "COM") (pinfunction "A_COM") (pintype "bidirectional"))
      (node (ref "B11ALT") (pin "COM") (pinfunction "A_COM") (pintype "bidirectional"))
      (node (ref "B12") (pin "COM") (pinfunction "A_COM") (pintype "bidirectional"))
      (node (ref "B12ALT") (pin "COM") (pinfunction "A_COM") (pintype "bidirectional"))
      (node (ref "B13") (pin "COM") (pinfunction "A_COM") (pintype "bidirectional"))
      (node (ref "B14") (pin "COM") (pinfunction "A_COM") (pintype "bidirectional"))
      (node (ref "B14ALT") (pin "COM") (pinfunction "A_COM") (pintype "bidirectional"))
      (node (ref "B15") (pin "COM") (pinfunction "A_COM") (pintype "bidirectional"))
      (node (ref "B16") (pin "COM") (pinfunction "A_COM") (pintype "bidirectional"))
      (node (ref "B17") (pin "COM") (pinfunction "A_COM") (pintype "bidirectional"))
      (node (ref "B17ALT") (pin "COM") (pinfunction "A_COM") (pintype "bidirectional"))
      (node (ref "B18") (pin "COM") (pinfunction "A_COM") (pintype "bidirectional"))
      (node (ref "B19") (pin "COM") (pinfunction "A_COM") (pintype "bidirectional"))
      (node (ref "B1ALT") (pin "COM") (pinfunction "A_COM") (pintype "bidirectional"))
      (node (ref "B2") (pin "COM") (pinfunction "A_COM") (pintype "bidirectional"))
      (node (ref "B20") (pin "COM") (pinfunction "A_COM") (pintype "bidirectional"))
      (node (ref "B20ALT") (pin "COM") (pinfunction "A_COM") (pintype "bidirectional"))
      (node (ref "B21") (pin "COM") (pinfunction "A_COM") (pintype "bidirectional"))
      (node (ref "B21ALT") (pin "COM") (pinfunction "A_COM") (pintype "bidirectional"))
      (node (ref "B22") (pin "COM") (pinfunction "A_COM") (pintype "bidirectional"))
      (node (ref "B23") (pin "COM") (pinfunction "A_COM") (pintype "bidirectional"))
      (node (ref "B24") (pin "COM") (pinfunction "A_COM") (pintype "bidirectional"))
      (node (ref "B25") (pin "COM") (pinfunction "A_COM") (pintype "bidirectional"))
      (node (ref "B26") (pin "COM") (pinfunction "A_COM") (pintype "bidirectional"))
      (node (ref "B26ALT") (pin "COM") (pinfunction "A_COM") (pintype "bidirectional"))
      (node (ref "B27") (pin "COM") (pinfunction "A_COM") (pintype "bidirectional"))
      (node (ref "B27ALT") (pin "COM") (pinfunction "A_COM") (pintype "bidirectional"))
      (node (ref "B28") (pin "COM") (pinfunction "A_COM") (pintype "bidirectional"))
      (node (ref "B29") (pin "COM") (pinfunction "A_COM") (pintype "bidirectional"))
      (node (ref "B2ALT") (pin "COM") (pinfunction "A_COM") (pintype "bidirectional"))
      (node (ref "B3") (pin "COM") (pinfunction "A_COM") (pintype "bidirectional"))
      (node (ref "B30") (pin "COM") (pinfunction "A_COM") (pintype "bidirectional"))
      (node (ref "B3ALT") (pin "COM") (pinfunction "A_COM") (pintype "bidirectional"))
      (node (ref "B4") (pin "COM") (pinfunction "A_COM") (pintype "bidirectional"))
      (node (ref "B4ALT") (pin "COM") (pinfunction "A_COM") (pintype "bidirectional"))
      (node (ref "B5") (pin "COM") (pinfunction "A_COM") (pintype "bidirectional"))
      (node (ref "B5ALT") (pin "COM") (pinfunction "A_COM") (pintype "bidirectional"))
      (node (ref "B6") (pin "COM") (pinfunction "A_COM") (pintype "bidirectional"))
      (node (ref "B6ALT") (pin "COM") (pinfunction "A_COM") (pintype "bidirectional"))
      (node (ref "B7") (pin "COM") (pinfunction "A_COM") (pintype "bidirectional"))
      (node (ref "B7ALT") (pin "COM") (pinfunction "A_COM") (pintype "bidirectional"))
      (node (ref "B8") (pin "COM") (pinfunction "A_COM") (pintype "bidirectional"))
      (node (ref "B8ALT") (pin "COM") (pinfunction "A_COM") (pintype "bidirectional"))
      (node (ref "B9") (pin "COM") (pinfunction "A_COM") (pintype "bidirectional"))
      (node (ref "B9ALT") (pin "COM") (pinfunction "A_COM") (pintype "bidirectional"))
      (node (ref "C10") (pin "1") (pinfunction "1_1") (pintype "passive"))
      (node (ref "C11") (pin "1") (pinfunction "1_1") (pintype "passive"))
      (node (ref "C12") (pin "1") (pinfunction "1_1") (pintype "passive"))
      (node (ref "C13") (pin "1") (pinfunction "1_1") (pintype "passive"))
      (node (ref "C14") (pin "1") (pinfunction "1_1") (pintype "passive"))
      (node (ref "C15") (pin "2") (pinfunction "2_2") (pintype "passive"))
      (node (ref "C16") (pin "1") (pinfunction "1_1") (pintype "passive"))
      (node (ref "C17") (pin "1") (pinfunction "1_1") (pintype "passive"))
      (node (ref "C18") (pin "1") (pinfunction "1_1") (pintype "passive"))
      (node (ref "C19") (pin "1") (pinfunction "1_1") (pintype "passive"))
      (node (ref "C20") (pin "1") (pinfunction "1_1") (pintype "passive"))
      (node (ref "C21") (pin "2") (pinfunction "2_2") (pintype "passive"))
      (node (ref "C22") (pin "1") (pinfunction "1_1") (pintype "passive"))
      (node (ref "C23") (pin "1") (pinfunction "1_1") (pintype "passive"))
      (node (ref "C27") (pin "1") (pinfunction "1_1") (pintype "passive"))
      (node (ref "C30") (pin "2") (pinfunction "2_2") (pintype "passive"))
      (node (ref "C4") (pin "2") (pinfunction "2_2") (pintype "passive"))
      (node (ref "C5") (pin "1") (pinfunction "1_1") (pintype "passive"))
      (node (ref "C7") (pin "1") (pinfunction "1_1") (pintype "passive"))
      (node (ref "C8") (pin "1") (pinfunction "1_1") (pintype "passive"))
      (node (ref "C9") (pin "1") (pinfunction "1_1") (pintype "passive"))
      (node (ref "IC1") (pin "18") (pinfunction "~{RESET}_18") (pintype "input"))
      (node (ref "IC1") (pin "9") (pinfunction "VDD_9") (pintype "power_in"))
      (node (ref "IC2") (pin "24") (pinfunction "A5_24") (pintype "input"))
      (node (ref "IC2") (pin "28") (pinfunction "VDD_28") (pintype "power_in"))
      (node (ref "IC2") (pin "4") (pinfunction "A3_4") (pintype "input"))
      (node (ref "IC2") (pin "5") (pinfunction "A4_5") (pintype "input"))
      (node (ref "IC3") (pin "24") (pinfunction "A5_24") (pintype "input"))
      (node (ref "IC3") (pin "28") (pinfunction "VDD_28") (pintype "power_in"))
      (node (ref "IC4") (pin "1") (pinfunction "A0_1") (pintype "input"))
      (node (ref "IC4") (pin "24") (pinfunction "A5_24") (pintype "input"))
      (node (ref "IC4") (pin "28") (pinfunction "VDD_28") (pintype "power_in"))
      (node (ref "IC4") (pin "4") (pinfunction "A3_4") (pintype "input"))
      (node (ref "IC4") (pin "5") (pinfunction "A4_5") (pintype "input"))
      (node (ref "IC5") (pin "1") (pinfunction "A0_1") (pintype "input"))
      (node (ref "IC5") (pin "24") (pinfunction "A5_24") (pintype "input"))
      (node (ref "IC5") (pin "28") (pinfunction "VDD_28") (pintype "power_in"))
      (node (ref "IC6") (pin "15") (pinfunction "A0_15") (pintype "input"))
      (node (ref "IC6") (pin "18") (pinfunction "~{RESET}_18") (pintype "input"))
      (node (ref "IC6") (pin "9") (pinfunction "VDD_9") (pintype "power_in"))
      (node (ref "IC7") (pin "16") (pinfunction "A1_16") (pintype "input"))
      (node (ref "IC7") (pin "18") (pinfunction "~{RESET}_18") (pintype "input"))
      (node (ref "IC7") (pin "9") (pinfunction "VDD_9") (pintype "power_in"))
      (node (ref "IC8") (pin "15") (pinfunction "A0_15") (pintype "input"))
      (node (ref "IC8") (pin "16") (pinfunction "A1_16") (pintype "input"))
      (node (ref "IC8") (pin "18") (pinfunction "~{RESET}_18") (pintype "input"))
      (node (ref "IC8") (pin "9") (pinfunction "VDD_9") (pintype "power_in"))
      (node (ref "IC9") (pin "14") (pinfunction "VCC_14") (pintype "power_in"))
      (node (ref "JP3") (pin "2") (pinfunction "2_2") (pintype "passive"))
      (node (ref "JP3") (pin "3") (pinfunction "3_3") (pintype "passive"))
      (node (ref "JP4") (pin "3") (pinfunction "3_3") (pintype "passive"))
      (node (ref "PC2") (pin "+") (pinfunction "+_+") (pintype "passive"))
      (node (ref "POT1") (pin "1") (pinfunction "E_1") (pintype "passive"))
      (node (ref "R58") (pin "2") (pinfunction "2_2") (pintype "passive"))
      (node (ref "SSW1") (pin "4") (pinfunction "VDD_4") (pintype "bidirectional"))
      (node (ref "SSW2") (pin "4") (pinfunction "VDD_4") (pintype "bidirectional"))
      (node (ref "U$34") (pin "H2") (pinfunction "VCC_H2") (pintype "passive"))
      (node (ref "U$34") (pin "H3") (pinfunction "VCC_H3") (pintype "passive"))
    )
    (net (code "2") (name "5V_RAW") (class "Default")
      (node (ref "C3") (pin "1") (pinfunction "1_1") (pintype "passive"))
      (node (ref "C6") (pin "1") (pinfunction "1_1") (pintype "passive"))
      (node (ref "L2") (pin "2") (pinfunction "2_2") (pintype "passive"))
    )
    (net (code "3") (name "A0") (class "Default")
      (node (ref "JP4") (pin "2") (pinfunction "2_2") (pintype "passive"))
      (node (ref "POT1") (pin "2A") (pinfunction "S_2A") (pintype "passive"))
      (node (ref "SERIAL2") (pin "5") (pinfunction "5_5") (pintype "passive"))
    )
    (net (code "4") (name "A2") (class "Default")
      (node (ref "IC1") (pin "17") (pinfunction "A2_17") (pintype "input"))
      (node (ref "IC2") (pin "3") (pinfunction "A2_3") (pintype "input"))
      (node (ref "IC3") (pin "3") (pinfunction "A2_3") (pintype "input"))
      (node (ref "IC4") (pin "3") (pinfunction "A2_3") (pintype "input"))
      (node (ref "IC5") (pin "3") (pinfunction "A2_3") (pintype "input"))
      (node (ref "IC6") (pin "17") (pinfunction "A2_17") (pintype "input"))
      (node (ref "IC7") (pin "17") (pinfunction "A2_17") (pintype "input"))
      (node (ref "IC8") (pin "17") (pinfunction "A2_17") (pintype "input"))
      (node (ref "U$34") (pin "A2") (pinfunction "A2_A2") (pintype "passive"))
    )
    (net (code "5") (name "AD0") (class "Default")
      (node (ref "C26") (pin "1") (pinfunction "1_1") (pintype "passive"))
      (node (ref "IC8") (pin "1") (pinfunction "GPB0_1") (pintype "bidirectional"))
      (node (ref "SW1") (pin "E") (pinfunction "2_E") (pintype "passive"))
      (node (ref "U$66") (pin "4") (pinfunction "4_4") (pintype "passive"))
    )
    (net (code "6") (name "D2") (class "Default")
      (node (ref "IC8") (pin "21") (pinfunction "GPA0_21") (pintype "bidirectional"))
      (node (ref "IC9") (pin "12") (pinfunction "O_12") (pintype "output"))
    )
    (net (code "7") (name "D3") (class "Default")
      (node (ref "C25") (pin "1") (pinfunction "1_1") (pintype "passive"))
      (node (ref "IC8") (pin "22") (pinfunction "GPA1_22") (pintype "bidirectional"))
      (node (ref "SW1") (pin "A") (pinfunction "A_A") (pintype "passive"))
      (node (ref "U$66") (pin "3") (pinfunction "3_3") (pintype "passive"))
    )
    (net (code "8") (name "GND") (class "Default")
      (node (ref "B1") (pin "P$4") (pinfunction "SW1_P$4") (pintype "bidirectional"))
      (node (ref "B10") (pin "P$4") (pinfunction "SW1_P$4") (pintype "bidirectional"))
      (node (ref "B10ALT") (pin "P$4") (pinfunction "SW1_P$4") (pintype "bidirectional"))
      (node (ref "B11") (pin "P$4") (pinfunction "SW1_P$4") (pintype "bidirectional"))
      (node (ref "B11ALT") (pin "P$4") (pinfunction "SW1_P$4") (pintype "bidirectional"))
      (node (ref "B12") (pin "P$4") (pinfunction "SW1_P$4") (pintype "bidirectional"))
      (node (ref "B12ALT") (pin "P$4") (pinfunction "SW1_P$4") (pintype "bidirectional"))
      (node (ref "B13") (pin "P$4") (pinfunction "SW1_P$4") (pintype "bidirectional"))
      (node (ref "B14") (pin "P$4") (pinfunction "SW1_P$4") (pintype "bidirectional"))
      (node (ref "B14ALT") (pin "P$4") (pinfunction "SW1_P$4") (pintype "bidirectional"))
      (node (ref "B15") (pin "P$4") (pinfunction "SW1_P$4") (pintype "bidirectional"))
      (node (ref "B16") (pin "P$4") (pinfunction "SW1_P$4") (pintype "bidirectional"))
      (node (ref "B17") (pin "P$4") (pinfunction "SW1_P$4") (pintype "bidirectional"))
      (node (ref "B17ALT") (pin "P$4") (pinfunction "SW1_P$4") (pintype "bidirectional"))
      (node (ref "B18") (pin "P$4") (pinfunction "SW1_P$4") (pintype "bidirectional"))
      (node (ref "B19") (pin "P$4") (pinfunction "SW1_P$4") (pintype "bidirectional"))
      (node (ref "B1ALT") (pin "P$4") (pinfunction "SW1_P$4") (pintype "bidirectional"))
      (node (ref "B2") (pin "P$4") (pinfunction "SW1_P$4") (pintype "bidirectional"))
      (node (ref "B20") (pin "P$4") (pinfunction "SW1_P$4") (pintype "bidirectional"))
      (node (ref "B20ALT") (pin "P$4") (pinfunction "SW1_P$4") (pintype "bidirectional"))
      (node (ref "B21") (pin "P$4") (pinfunction "SW1_P$4") (pintype "bidirectional"))
      (node (ref "B21ALT") (pin "P$4") (pinfunction "SW1_P$4") (pintype "bidirectional"))
      (node (ref "B22") (pin "P$4") (pinfunction "SW1_P$4") (pintype "bidirectional"))
      (node (ref "B23") (pin "P$4") (pinfunction "SW1_P$4") (pintype "bidirectional"))
      (node (ref "B24") (pin "P$4") (pinfunction "SW1_P$4") (pintype "bidirectional"))
      (node (ref "B25") (pin "P$4") (pinfunction "SW1_P$4") (pintype "bidirectional"))
      (node (ref "B26") (pin "P$4") (pinfunction "SW1_P$4") (pintype "bidirectional"))
      (node (ref "B26ALT") (pin "P$4") (pinfunction "SW1_P$4") (pintype "bidirectional"))
      (node (ref "B27") (pin "P$4") (pinfunction "SW1_P$4") (pintype "bidirectional"))
      (node (ref "B27ALT") (pin "P$4") (pinfunction "SW1_P$4") (pintype "bidirectional"))
      (node (ref "B28") (pin "P$4") (pinfunction "SW1_P$4") (pintype "bidirectional"))
      (node (ref "B29") (pin "P$4") (pinfunction "SW1_P$4") (pintype "bidirectional"))
      (node (ref "B2ALT") (pin "P$4") (pinfunction "SW1_P$4") (pintype "bidirectional"))
      (node (ref "B3") (pin "P$4") (pinfunction "SW1_P$4") (pintype "bidirectional"))
      (node (ref "B30") (pin "P$4") (pinfunction "SW1_P$4") (pintype "bidirectional"))
      (node (ref "B3ALT") (pin "P$4") (pinfunction "SW1_P$4") (pintype "bidirectional"))
      (node (ref "B4") (pin "P$4") (pinfunction "SW1_P$4") (pintype "bidirectional"))
      (node (ref "B4ALT") (pin "P$4") (pinfunction "SW1_P$4") (pintype "bidirectional"))
      (node (ref "B5") (pin "P$4") (pinfunction "SW1_P$4") (pintype "bidirectional"))
      (node (ref "B5ALT") (pin "P$4") (pinfunction "SW1_P$4") (pintype "bidirectional"))
      (node (ref "B6") (pin "P$4") (pinfunction "SW1_P$4") (pintype "bidirectional"))
      (node (ref "B6ALT") (pin "P$4") (pinfunction "SW1_P$4") (pintype "bidirectional"))
      (node (ref "B7") (pin "P$4") (pinfunction "SW1_P$4") (pintype "bidirectional"))
      (node (ref "B7ALT") (pin "P$4") (pinfunction "SW1_P$4") (pintype "bidirectional"))
      (node (ref "B8") (pin "P$4") (pinfunction "SW1_P$4") (pintype "bidirectional"))
      (node (ref "B8ALT") (pin "P$4") (pinfunction "SW1_P$4") (pintype "bidirectional"))
      (node (ref "B9") (pin "P$4") (pinfunction "SW1_P$4") (pintype "bidirectional"))
      (node (ref "B9ALT") (pin "P$4") (pinfunction "SW1_P$4") (pintype "bidirectional"))
      (node (ref "C10") (pin "2") (pinfunction "2_2") (pintype "passive"))
      (node (ref "C11") (pin "2") (pinfunction "2_2") (pintype "passive"))
      (node (ref "C12") (pin "2") (pinfunction "2_2") (pintype "passive"))
      (node (ref "C13") (pin "2") (pinfunction "2_2") (pintype "passive"))
      (node (ref "C14") (pin "2") (pinfunction "2_2") (pintype "passive"))
      (node (ref "C15") (pin "1") (pinfunction "1_1") (pintype "passive"))
      (node (ref "C16") (pin "2") (pinfunction "2_2") (pintype "passive"))
      (node (ref "C17") (pin "2") (pinfunction "2_2") (pintype "passive"))
      (node (ref "C18") (pin "2") (pinfunction "2_2") (pintype "passive"))
      (node (ref "C19") (pin "2") (pinfunction "2_2") (pintype "passive"))
      (node (ref "C20") (pin "2") (pinfunction "2_2") (pintype "passive"))
      (node (ref "C21") (pin "1") (pinfunction "1_1") (pintype "passive"))
      (node (ref "C22") (pin "2") (pinfunction "2_2") (pintype "passive"))
      (node (ref "C23") (pin "2") (pinfunction "2_2") (pintype "passive"))
      (node (ref "C24") (pin "2") (pinfunction "2_2") (pintype "passive"))
      (node (ref "C25") (pin "2") (pinfunction "2_2") (pintype "passive"))
      (node (ref "C26") (pin "2") (pinfunction "2_2") (pintype "passive"))
      (node (ref "C27") (pin "2") (pinfunction "2_2") (pintype "passive"))
      (node (ref "C3") (pin "2") (pinfunction "2_2") (pintype "passive"))
      (node (ref "C30") (pin "1") (pinfunction "1_1") (pintype "passive"))
      (node (ref "C4") (pin "1") (pinfunction "1_1") (pintype "passive"))
      (node (ref "C5") (pin "2") (pinfunction "2_2") (pintype "passive"))
      (node (ref "C6") (pin "2") (pinfunction "2_2") (pintype "passive"))
      (node (ref "C7") (pin "2") (pinfunction "2_2") (pintype "passive"))
      (node (ref "C8") (pin "2") (pinfunction "2_2") (pintype "passive"))
      (node (ref "C9") (pin "2") (pinfunction "2_2") (pintype "passive"))
      (node (ref "IC1") (pin "10") (pinfunction "VSS_10") (pintype "power_in"))
      (node (ref "IC1") (pin "15") (pinfunction "A0_15") (pintype "input"))
      (node (ref "IC1") (pin "16") (pinfunction "A1_16") (pintype "input"))
      (node (ref "IC2") (pin "1") (pinfunction "A0_1") (pintype "input"))
      (node (ref "IC2") (pin "14") (pinfunction "GND_14") (pintype "power_in"))
      (node (ref "IC2") (pin "2") (pinfunction "A1_2") (pintype "input"))
      (node (ref "IC2") (pin "23") (pinfunction "OE_23") (pintype "input"))
      (node (ref "IC2") (pin "25") (pinfunction "EXTCLK_25") (pintype "input"))
      (node (ref "IC3") (pin "1") (pinfunction "A0_1") (pintype "input"))
      (node (ref "IC3") (pin "14") (pinfunction "GND_14") (pintype "power_in"))
      (node (ref "IC3") (pin "2") (pinfunction "A1_2") (pintype "input"))
      (node (ref "IC3") (pin "23") (pinfunction "OE_23") (pintype "input"))
      (node (ref "IC3") (pin "25") (pinfunction "EXTCLK_25") (pintype "input"))
      (node (ref "IC3") (pin "4") (pinfunction "A3_4") (pintype "input"))
      (node (ref "IC3") (pin "5") (pinfunction "A4_5") (pintype "input"))
      (node (ref "IC4") (pin "14") (pinfunction "GND_14") (pintype "power_in"))
      (node (ref "IC4") (pin "2") (pinfunction "A1_2") (pintype "input"))
      (node (ref "IC4") (pin "23") (pinfunction "OE_23") (pintype "input"))
      (node (ref "IC4") (pin "25") (pinfunction "EXTCLK_25") (pintype "input"))
      (node (ref "IC5") (pin "14") (pinfunction "GND_14") (pintype "power_in"))
      (node (ref "IC5") (pin "2") (pinfunction "A1_2") (pintype "input"))
      (node (ref "IC5") (pin "23") (pinfunction "OE_23") (pintype "input"))
      (node (ref "IC5") (pin "25") (pinfunction "EXTCLK_25") (pintype "input"))
      (node (ref "IC5") (pin "4") (pinfunction "A3_4") (pintype "input"))
      (node (ref "IC5") (pin "5") (pinfunction "A4_5") (pintype "input"))
      (node (ref "IC6") (pin "10") (pinfunction "VSS_10") (pintype "power_in"))
      (node (ref "IC6") (pin "16") (pinfunction "A1_16") (pintype "input"))
      (node (ref "IC7") (pin "10") (pinfunction "VSS_10") (pintype "power_in"))
      (node (ref "IC7") (pin "15") (pinfunction "A0_15") (pintype "input"))
      (node (ref "IC8") (pin "10") (pinfunction "VSS_10") (pintype "power_in"))
      (node (ref "IC9") (pin "1") (pinfunction "I_1") (pintype "input"))
      (node (ref "IC9") (pin "11") (pinfunction "I_11") (pintype "input"))
      (node (ref "IC9") (pin "3") (pinfunction "I_3") (pintype "input"))
      (node (ref "IC9") (pin "5") (pinfunction "I_5") (pintype "input"))
      (node (ref "IC9") (pin "7") (pinfunction "GND_7") (pintype "power_in"))
      (node (ref "IC9") (pin "9") (pinfunction "I_9") (pintype "input"))
      (node (ref "JP3") (pin "1") (pinfunction "1_1") (pintype "passive"))
      (node (ref "JP3") (pin "4") (pinfunction "4_4") (pintype "passive"))
      (node (ref "JP4") (pin "1") (pinfunction "1_1") (pintype "passive"))
      (node (ref "JP4") (pin "4") (pinfunction "4_4") (pintype "passive"))
      (node (ref "PC2") (pin "-") (pinfunction "-_-") (pintype "passive"))
      (node (ref "POT1") (pin "3") (pinfunction "A_3") (pintype "passive"))
      (node (ref "SERIAL2") (pin "1") (pinfunction "1_1") (pintype "passive"))
      (node (ref "SSW1") (pin "1") (pinfunction "SW1_1") (pintype "bidirectional"))
      (node (ref "SSW1") (pin "3") (pinfunction "GND_3") (pintype "bidirectional"))
      (node (ref "SSW2") (pin "1") (pinfunction "SW1_1") (pintype "bidirectional"))
      (node (ref "SSW2") (pin "3") (pinfunction "GND_3") (pintype "bidirectional"))
      (node (ref "SW1") (pin "C") (pinfunction "C_C") (pintype "passive"))
      (node (ref "SW1") (pin "D") (pinfunction "1_D") (pintype "passive"))
      (node (ref "U$15") (pin "P$1") (pinfunction "1_P$1") (pintype "passive"))
      (node (ref "U$18") (pin "P$1") (pinfunction "1_P$1") (pintype "passive"))
      (node (ref "U$20") (pin "P$1") (pinfunction "1_P$1") (pintype "passive"))
      (node (ref "U$21") (pin "P$1") (pinfunction "1_P$1") (pintype "passive"))
      (node (ref "U$34") (pin "L2") (pinfunction "GND_L2") (pintype "passive"))
      (node (ref "U$34") (pin "L3") (pinfunction "GND_L3") (pintype "passive"))
      (node (ref "U$66") (pin "1") (pinfunction "1_1") (pintype "passive"))
      (node (ref "U$7") (pin "P$1") (pinfunction "1_P$1") (pintype "passive"))
    )
    (net (code "9") (name "GPA0") (class "Default")
      (node (ref "B8") (pin "P$5") (pinfunction "SW2_P$5") (pintype "bidirectional"))
      (node (ref "B8ALT") (pin "P$5") (pinfunction "SW2_P$5") (pintype "bidirectional"))
      (node (ref "IC1") (pin "21") (pinfunction "GPA0_21") (pintype "bidirectional"))
    )
    (net (code "10") (name "GPA0_2") (class "Default")
      (node (ref "IC7") (pin "21") (pinfunction "GPA0_21") (pintype "bidirectional"))
      (node (ref "SSW1") (pin "2") (pinfunction "SW2_2") (pintype "bidirectional"))
    )
    (net (code "11") (name "GPA1") (class "Default")
      (node (ref "B7") (pin "P$5") (pinfunction "SW2_P$5") (pintype "bidirectional"))
      (node (ref "B7ALT") (pin "P$5") (pinfunction "SW2_P$5") (pintype "bidirectional"))
      (node (ref "IC1") (pin "22") (pinfunction "GPA1_22") (pintype "bidirectional"))
    )
    (net (code "12") (name "GPA1_2") (class "Default")
      (node (ref "IC7") (pin "22") (pinfunction "GPA1_22") (pintype "bidirectional"))
      (node (ref "SSW2") (pin "2") (pinfunction "SW2_2") (pintype "bidirectional"))
    )
    (net (code "13") (name "GPA2") (class "Default")
      (node (ref "B6") (pin "P$5") (pinfunction "SW2_P$5") (pintype "bidirectional"))
      (node (ref "B6ALT") (pin "P$5") (pinfunction "SW2_P$5") (pintype "bidirectional"))
      (node (ref "IC1") (pin "23") (pinfunction "GPA2_23") (pintype "bidirectional"))
    )
    (net (code "14") (name "GPA3") (class "Default")
      (node (ref "B5") (pin "P$5") (pinfunction "SW2_P$5") (pintype "bidirectional"))
      (node (ref "B5ALT") (pin "P$5") (pinfunction "SW2_P$5") (pintype "bidirectional"))
      (node (ref "IC1") (pin "24") (pinfunction "GPA3_24") (pintype "bidirectional"))
    )
    (net (code "15") (name "GPA4") (class "Default")
      (node (ref "B1") (pin "P$5") (pinfunction "SW2_P$5") (pintype "bidirectional"))
      (node (ref "B1ALT") (pin "P$5") (pinfunction "SW2_P$5") (pintype "bidirectional"))
      (node (ref "IC1") (pin "25") (pinfunction "GPA4_25") (pintype "bidirectional"))
    )
    (net (code "16") (name "GPA5") (class "Default")
      (node (ref "B2") (pin "P$5") (pinfunction "SW2_P$5") (pintype "bidirectional"))
      (node (ref "B2ALT") (pin "P$5") (pinfunction "SW2_P$5") (pintype "bidirectional"))
      (node (ref "IC1") (pin "26") (pinfunction "GPA5_26") (pintype "bidirectional"))
    )
    (net (code "17") (name "GPA6") (class "Default")
      (node (ref "B3") (pin "P$5") (pinfunction "SW2_P$5") (pintype "bidirectional"))
      (node (ref "B3ALT") (pin "P$5") (pinfunction "SW2_P$5") (pintype "bidirectional"))
      (node (ref "IC1") (pin "27") (pinfunction "GPA6_27") (pintype "bidirectional"))
    )
    (net (code "18") (name "GPA7") (class "Default")
      (node (ref "B4") (pin "P$5") (pinfunction "SW2_P$5") (pintype "bidirectional"))
      (node (ref "B4ALT") (pin "P$5") (pinfunction "SW2_P$5") (pintype "bidirectional"))
      (node (ref "IC1") (pin "28") (pinfunction "GPA7_28") (pintype "bidirectional"))
    )
    (net (code "19") (name "GPA8") (class "Default")
      (node (ref "B16") (pin "P$5") (pinfunction "SW2_P$5") (pintype "bidirectional"))
      (node (ref "IC1") (pin "1") (pinfunction "GPB0_1") (pintype "bidirectional"))
    )
    (net (code "20") (name "GPA9") (class "Default")
      (node (ref "B15") (pin "P$5") (pinfunction "SW2_P$5") (pintype "bidirectional"))
      (node (ref "IC1") (pin "2") (pinfunction "GPB1_2") (pintype "bidirectional"))
    )
    (net (code "21") (name "GPA10") (class "Default")
      (node (ref "B14") (pin "P$5") (pinfunction "SW2_P$5") (pintype "bidirectional"))
      (node (ref "B14ALT") (pin "P$5") (pinfunction "SW2_P$5") (pintype "bidirectional"))
      (node (ref "IC1") (pin "3") (pinfunction "GPB2_3") (pintype "bidirectional"))
    )
    (net (code "22") (name "GPA11") (class "Default")
      (node (ref "B13") (pin "P$5") (pinfunction "SW2_P$5") (pintype "bidirectional"))
      (node (ref "IC1") (pin "4") (pinfunction "GPB3_4") (pintype "bidirectional"))
    )
    (net (code "23") (name "GPA12") (class "Default")
      (node (ref "B9") (pin "P$5") (pinfunction "SW2_P$5") (pintype "bidirectional"))
      (node (ref "B9ALT") (pin "P$5") (pinfunction "SW2_P$5") (pintype "bidirectional"))
      (node (ref "IC1") (pin "5") (pinfunction "GPB4_5") (pintype "bidirectional"))
    )
    (net (code "24") (name "GPA13") (class "Default")
      (node (ref "B10") (pin "P$5") (pinfunction "SW2_P$5") (pintype "bidirectional"))
      (node (ref "B10ALT") (pin "P$5") (pinfunction "SW2_P$5") (pintype "bidirectional"))
      (node (ref "IC1") (pin "6") (pinfunction "GPB5_6") (pintype "bidirectional"))
    )
    (net (code "25") (name "GPA14") (class "Default")
      (node (ref "B11") (pin "P$5") (pinfunction "SW2_P$5") (pintype "bidirectional"))
      (node (ref "B11ALT") (pin "P$5") (pinfunction "SW2_P$5") (pintype "bidirectional"))
      (node (ref "IC1") (pin "7") (pinfunction "GPB6_7") (pintype "bidirectional"))
    )
    (net (code "26") (name "GPA15") (class "Default")
      (node (ref "B12") (pin "P$5") (pinfunction "SW2_P$5") (pintype "bidirectional"))
      (node (ref "B12ALT") (pin "P$5") (pinfunction "SW2_P$5") (pintype "bidirectional"))
      (node (ref "IC1") (pin "8") (pinfunction "GPB7_8") (pintype "bidirectional"))
    )
    (net (code "27") (name "GPA16") (class "Default")
      (node (ref "B24") (pin "P$5") (pinfunction "SW2_P$5") (pintype "bidirectional"))
      (node (ref "IC6") (pin "21") (pinfunction "GPA0_21") (pintype "bidirectional"))
    )
    (net (code "28") (name "GPA17") (class "Default")
      (node (ref "B23") (pin "P$5") (pinfunction "SW2_P$5") (pintype "bidirectional"))
      (node (ref "IC6") (pin "22") (pinfunction "GPA1_22") (pintype "bidirectional"))
    )
    (net (code "29") (name "GPA18") (class "Default")
      (node (ref "B22") (pin "P$5") (pinfunction "SW2_P$5") (pintype "bidirectional"))
      (node (ref "IC6") (pin "23") (pinfunction "GPA2_23") (pintype "bidirectional"))
    )
    (net (code "30") (name "GPA19") (class "Default")
      (node (ref "B21") (pin "P$5") (pinfunction "SW2_P$5") (pintype "bidirectional"))
      (node (ref "B21ALT") (pin "P$5") (pinfunction "SW2_P$5") (pintype "bidirectional"))
      (node (ref "IC6") (pin "24") (pinfunction "GPA3_24") (pintype "bidirectional"))
    )
    (net (code "31") (name "GPA20") (class "Default")
      (node (ref "B17") (pin "P$5") (pinfunction "SW2_P$5") (pintype "bidirectional"))
      (node (ref "B17ALT") (pin "P$5") (pinfunction "SW2_P$5") (pintype "bidirectional"))
      (node (ref "IC6") (pin "25") (pinfunction "GPA4_25") (pintype "bidirectional"))
    )
    (net (code "32") (name "GPA21") (class "Default")
      (node (ref "B18") (pin "P$5") (pinfunction "SW2_P$5") (pintype "bidirectional"))
      (node (ref "IC6") (pin "26") (pinfunction "GPA5_26") (pintype "bidirectional"))
    )
    (net (code "33") (name "GPA22") (class "Default")
      (node (ref "B19") (pin "P$5") (pinfunction "SW2_P$5") (pintype "bidirectional"))
      (node (ref "IC6") (pin "27") (pinfunction "GPA6_27") (pintype "bidirectional"))
    )
    (net (code "34") (name "GPA23") (class "Default")
      (node (ref "B20") (pin "P$5") (pinfunction "SW2_P$5") (pintype "bidirectional"))
      (node (ref "B20ALT") (pin "P$5") (pinfunction "SW2_P$5") (pintype "bidirectional"))
      (node (ref "IC6") (pin "28") (pinfunction "GPA7_28") (pintype "bidirectional"))
    )
    (net (code "35") (name "GPA24") (class "Default")
      (node (ref "IC6") (pin "1") (pinfunction "GPB0_1") (pintype "bidirectional"))
    )
    (net (code "36") (name "GPA25") (class "Default")
      (node (ref "IC6") (pin "2") (pinfunction "GPB1_2") (pintype "bidirectional"))
    )
    (net (code "37") (name "GPA26") (class "Default")
      (node (ref "B30") (pin "P$5") (pinfunction "SW2_P$5") (pintype "bidirectional"))
      (node (ref "IC6") (pin "3") (pinfunction "GPB2_3") (pintype "bidirectional"))
    )
    (net (code "38") (name "GPA27") (class "Default")
      (node (ref "B29") (pin "P$5") (pinfunction "SW2_P$5") (pintype "bidirectional"))
      (node (ref "IC6") (pin "4") (pinfunction "GPB3_4") (pintype "bidirectional"))
    )
    (net (code "39") (name "GPA28") (class "Default")
      (node (ref "B25") (pin "P$5") (pinfunction "SW2_P$5") (pintype "bidirectional"))
      (node (ref "IC6") (pin "5") (pinfunction "GPB4_5") (pintype "bidirectional"))
    )
    (net (code "40") (name "GPA29") (class "Default")
      (node (ref "B26") (pin "P$5") (pinfunction "SW2_P$5") (pintype "bidirectional"))
      (node (ref "B26ALT") (pin "P$5") (pinfunction "SW2_P$5") (pintype "bidirectional"))
      (node (ref "IC6") (pin "6") (pinfunction "GPB5_6") (pintype "bidirectional"))
    )
    (net (code "41") (name "GPA30") (class "Default")
      (node (ref "B27") (pin "P$5") (pinfunction "SW2_P$5") (pintype "bidirectional"))
      (node (ref "B27ALT") (pin "P$5") (pinfunction "SW2_P$5") (pintype "bidirectional"))
      (node (ref "IC6") (pin "7") (pinfunction "GPB6_7") (pintype "bidirectional"))
    )
    (net (code "42") (name "GPA31") (class "Default")
      (node (ref "B28") (pin "P$5") (pinfunction "SW2_P$5") (pintype "bidirectional"))
      (node (ref "IC6") (pin "8") (pinfunction "GPB7_8") (pintype "bidirectional"))
    )
    (net (code "43") (name "GPB0") (class "Default")
      (node (ref "IC7") (pin "1") (pinfunction "GPB0_1") (pintype "bidirectional"))
      (node (ref "SSW1") (pin "8") (pinfunction "SS_8") (pintype "bidirectional"))
    )
    (net (code "44") (name "GPB1") (class "Default")
      (node (ref "IC7") (pin "2") (pinfunction "GPB1_2") (pintype "bidirectional"))
      (node (ref "SSW2") (pin "8") (pinfunction "SS_8") (pintype "bidirectional"))
    )
    (net (code "45") (name "I2C_SCL") (class "Default")
      (node (ref "IC1") (pin "12") (pinfunction "SCL_12") (pintype "input"))
      (node (ref "IC2") (pin "26") (pinfunction "SCL_26") (pintype "input"))
      (node (ref "IC3") (pin "26") (pinfunction "SCL_26") (pintype "input"))
      (node (ref "IC4") (pin "26") (pinfunction "SCL_26") (pintype "input"))
      (node (ref "IC5") (pin "26") (pinfunction "SCL_26") (pintype "input"))
      (node (ref "IC6") (pin "12") (pinfunction "SCL_12") (pintype "input"))
      (node (ref "IC7") (pin "12") (pinfunction "SCL_12") (pintype "input"))
      (node (ref "IC8") (pin "12") (pinfunction "SCL_12") (pintype "input"))
      (node (ref "SERIAL2") (pin "4") (pinfunction "4_4") (pintype "passive"))
    )
    (net (code "46") (name "I2C_SDA") (class "Default")
      (node (ref "IC1") (pin "13") (pinfunction "SDA_13") (pintype "bidirectional"))
      (node (ref "IC2") (pin "27") (pinfunction "SDA_27") (pintype "input"))
      (node (ref "IC3") (pin "27") (pinfunction "SDA_27") (pintype "input"))
      (node (ref "IC4") (pin "27") (pinfunction "SDA_27") (pintype "input"))
      (node (ref "IC5") (pin "27") (pinfunction "SDA_27") (pintype "input"))
      (node (ref "IC6") (pin "13") (pinfunction "SDA_13") (pintype "bidirectional"))
      (node (ref "IC7") (pin "13") (pinfunction "SDA_13") (pintype "bidirectional"))
      (node (ref "IC8") (pin "13") (pinfunction "SDA_13") (pintype "bidirectional"))
      (node (ref "SERIAL2") (pin "3") (pinfunction "3_3") (pintype "passive"))
    )
    (net (code "47") (name "L0") (class "Default")
      (node (ref "B1") (pin "P$2") (pinfunction "K1_P$2") (pintype "bidirectional"))
      (node (ref "B1ALT") (pin "P$2") (pinfunction "K1_P$2") (pintype "bidirectional"))
      (node (ref "R23") (pin "1") (pinfunction "1_1") (pintype "passive"))
    )
    (net (code "48") (name "L1") (class "Default")
      (node (ref "B1") (pin "P$3") (pinfunction "K2_P$3") (pintype "bidirectional"))
      (node (ref "B1ALT") (pin "P$3") (pinfunction "K2_P$3") (pintype "bidirectional"))
      (node (ref "R22") (pin "1") (pinfunction "1_1") (pintype "passive"))
    )
    (net (code "49") (name "L2") (class "Default")
      (node (ref "B2") (pin "P$2") (pinfunction "K1_P$2") (pintype "bidirectional"))
      (node (ref "B2ALT") (pin "P$2") (pinfunction "K1_P$2") (pintype "bidirectional"))
      (node (ref "R21") (pin "1") (pinfunction "1_1") (pintype "passive"))
    )
    (net (code "50") (name "L3") (class "Default")
      (node (ref "B2") (pin "P$3") (pinfunction "K2_P$3") (pintype "bidirectional"))
      (node (ref "B2ALT") (pin "P$3") (pinfunction "K2_P$3") (pintype "bidirectional"))
      (node (ref "R20") (pin "1") (pinfunction "1_1") (pintype "passive"))
    )
    (net (code "51") (name "L4") (class "Default")
      (node (ref "B3") (pin "P$2") (pinfunction "K1_P$2") (pintype "bidirectional"))
      (node (ref "B3ALT") (pin "P$2") (pinfunction "K1_P$2") (pintype "bidirectional"))
      (node (ref "R19") (pin "1") (pinfunction "1_1") (pintype "passive"))
    )
    (net (code "52") (name "L5") (class "Default")
      (node (ref "B3") (pin "P$3") (pinfunction "K2_P$3") (pintype "bidirectional"))
      (node (ref "B3ALT") (pin "P$3") (pinfunction "K2_P$3") (pintype "bidirectional"))
      (node (ref "R18") (pin "1") (pinfunction "1_1") (pintype "passive"))
    )
    (net (code "53") (name "L6") (class "Default")
      (node (ref "B4") (pin "P$2") (pinfunction "K1_P$2") (pintype "bidirectional"))
      (node (ref "B4ALT") (pin "P$2") (pinfunction "K1_P$2") (pintype "bidirectional"))
      (node (ref "R17") (pin "1") (pinfunction "1_1") (pintype "passive"))
    )
    (net (code "54") (name "L7") (class "Default")
      (node (ref "B4") (pin "P$3") (pinfunction "K2_P$3") (pintype "bidirectional"))
      (node (ref "B4ALT") (pin "P$3") (pinfunction "K2_P$3") (pintype "bidirectional"))
      (node (ref "R16") (pin "1") (pinfunction "1_1") (pintype "passive"))
    )
    (net (code "55") (name "L8") (class "Default")
      (node (ref "B5") (pin "P$2") (pinfunction "K1_P$2") (pintype "bidirectional"))
      (node (ref "B5ALT") (pin "P$2") (pinfunction "K1_P$2") (pintype "bidirectional"))
      (node (ref "R15") (pin "1") (pinfunction "1_1") (pintype "passive"))
    )
    (net (code "56") (name "L9") (class "Default")
      (node (ref "B5") (pin "P$3") (pinfunction "K2_P$3") (pintype "bidirectional"))
      (node (ref "B5ALT") (pin "P$3") (pinfunction "K2_P$3") (pintype "bidirectional"))
      (node (ref "R14") (pin "1") (pinfunction "1_1") (pintype "passive"))
    )
    (net (code "57") (name "L10") (class "Default")
      (node (ref "B6") (pin "P$2") (pinfunction "K1_P$2") (pintype "bidirectional"))
      (node (ref "B6ALT") (pin "P$2") (pinfunction "K1_P$2") (pintype "bidirectional"))
      (node (ref "R13") (pin "1") (pinfunction "1_1") (pintype "passive"))
    )
    (net (code "58") (name "L11") (class "Default")
      (node (ref "B6") (pin "P$3") (pinfunction "K2_P$3") (pintype "bidirectional"))
      (node (ref "B6ALT") (pin "P$3") (pinfunction "K2_P$3") (pintype "bidirectional"))
      (node (ref "R12") (pin "1") (pinfunction "1_1") (pintype "passive"))
    )
    (net (code "59") (name "L12") (class "Default")
      (node (ref "B7") (pin "P$2") (pinfunction "K1_P$2") (pintype "bidirectional"))
      (node (ref "B7ALT") (pin "P$2") (pinfunction "K1_P$2") (pintype "bidirectional"))
      (node (ref "R11") (pin "1") (pinfunction "1_1") (pintype "passive"))
    )
    (net (code "60") (name "L13") (class "Default")
      (node (ref "B7") (pin "P$3") (pinfunction "K2_P$3") (pintype "bidirectional"))
      (node (ref "B7ALT") (pin "P$3") (pinfunction "K2_P$3") (pintype "bidirectional"))
      (node (ref "R10") (pin "1") (pinfunction "1_1") (pintype "passive"))
    )
    (net (code "61") (name "L14") (class "Default")
      (node (ref "B8") (pin "P$2") (pinfunction "K1_P$2") (pintype "bidirectional"))
      (node (ref "B8ALT") (pin "P$2") (pinfunction "K1_P$2") (pintype "bidirectional"))
      (node (ref "R4") (pin "1") (pinfunction "1_1") (pintype "passive"))
    )
    (net (code "62") (name "L15") (class "Default")
      (node (ref "B8") (pin "P$3") (pinfunction "K2_P$3") (pintype "bidirectional"))
      (node (ref "B8ALT") (pin "P$3") (pinfunction "K2_P$3") (pintype "bidirectional"))
      (node (ref "R3") (pin "1") (pinfunction "1_1") (pintype "passive"))
    )
    (net (code "63") (name "L16") (class "Default")
      (node (ref "B9") (pin "P$2") (pinfunction "K1_P$2") (pintype "bidirectional"))
      (node (ref "B9ALT") (pin "P$2") (pinfunction "K1_P$2") (pintype "bidirectional"))
      (node (ref "R39") (pin "1") (pinfunction "1_1") (pintype "passive"))
    )
    (net (code "64") (name "L17") (class "Default")
      (node (ref "B9") (pin "P$3") (pinfunction "K2_P$3") (pintype "bidirectional"))
      (node (ref "B9ALT") (pin "P$3") (pinfunction "K2_P$3") (pintype "bidirectional"))
      (node (ref "R38") (pin "1") (pinfunction "1_1") (pintype "passive"))
    )
    (net (code "65") (name "L18") (class "Default")
      (node (ref "B10") (pin "P$2") (pinfunction "K1_P$2") (pintype "bidirectional"))
      (node (ref "B10ALT") (pin "P$2") (pinfunction "K1_P$2") (pintype "bidirectional"))
      (node (ref "R37") (pin "1") (pinfunction "1_1") (pintype "passive"))
    )
    (net (code "66") (name "L19") (class "Default")
      (node (ref "B10") (pin "P$3") (pinfunction "K2_P$3") (pintype "bidirectional"))
      (node (ref "B10ALT") (pin "P$3") (pinfunction "K2_P$3") (pintype "bidirectional"))
      (node (ref "R36") (pin "1") (pinfunction "1_1") (pintype "passive"))
    )
    (net (code "67") (name "L20") (class "Default")
      (node (ref "B11") (pin "P$2") (pinfunction "K1_P$2") (pintype "bidirectional"))
      (node (ref "B11ALT") (pin "P$2") (pinfunction "K1_P$2") (pintype "bidirectional"))
      (node (ref "R35") (pin "1") (pinfunction "1_1") (pintype "passive"))
    )
    (net (code "68") (name "L21") (class "Default")
      (node (ref "B11") (pin "P$3") (pinfunction "K2_P$3") (pintype "bidirectional"))
      (node (ref "B11ALT") (pin "P$3") (pinfunction "K2_P$3") (pintype "bidirectional"))
      (node (ref "R34") (pin "1") (pinfunction "1_1") (pintype "passive"))
    )
    (net (code "69") (name "L22") (class "Default")
      (node (ref "B12") (pin "P$2") (pinfunction "K1_P$2") (pintype "bidirectional"))
      (node (ref "B12ALT") (pin "P$2") (pinfunction "K1_P$2") (pintype "bidirectional"))
      (node (ref "R33") (pin "1") (pinfunction "1_1") (pintype "passive"))
    )
    (net (code "70") (name "L23") (class "Default")
      (node (ref "B12") (pin "P$3") (pinfunction "K2_P$3") (pintype "bidirectional"))
      (node (ref "B12ALT") (pin "P$3") (pinfunction "K2_P$3") (pintype "bidirectional"))
      (node (ref "R32") (pin "1") (pinfunction "1_1") (pintype "passive"))
    )
    (net (code "71") (name "L24") (class "Default")
      (node (ref "B13") (pin "P$2") (pinfunction "K1_P$2") (pintype "bidirectional"))
      (node (ref "R31") (pin "1") (pinfunction "1_1") (pintype "passive"))
    )
    (net (code "72") (name "L25") (class "Default")
      (node (ref "B13") (pin "P$3") (pinfunction "K2_P$3") (pintype "bidirectional"))
      (node (ref "R30") (pin "1") (pinfunction "1_1") (pintype "passive"))
    )
    (net (code "73") (name "L26") (class "Default")
      (node (ref "B14") (pin "P$2") (pinfunction "K1_P$2") (pintype "bidirectional"))
      (node (ref "B14ALT") (pin "P$2") (pinfunction "K1_P$2") (pintype "bidirectional"))
      (node (ref "R29") (pin "1") (pinfunction "1_1") (pintype "passive"))
    )
    (net (code "74") (name "L27") (class "Default")
      (node (ref "B14") (pin "P$3") (pinfunction "K2_P$3") (pintype "bidirectional"))
      (node (ref "B14ALT") (pin "P$3") (pinfunction "K2_P$3") (pintype "bidirectional"))
      (node (ref "R28") (pin "1") (pinfunction "1_1") (pintype "passive"))
    )
    (net (code "75") (name "L28") (class "Default")
      (node (ref "B15") (pin "P$2") (pinfunction "K1_P$2") (pintype "bidirectional"))
      (node (ref "R27") (pin "1") (pinfunction "1_1") (pintype "passive"))
    )
    (net (code "76") (name "L29") (class "Default")
      (node (ref "B15") (pin "P$3") (pinfunction "K2_P$3") (pintype "bidirectional"))
      (node (ref "R26") (pin "1") (pinfunction "1_1") (pintype "passive"))
    )
    (net (code "77") (name "L30") (class "Default")
      (node (ref "B16") (pin "P$2") (pinfunction "K1_P$2") (pintype "bidirectional"))
      (node (ref "R25") (pin "1") (pinfunction "1_1") (pintype "passive"))
    )
    (net (code "78") (name "L31") (class "Default")
      (node (ref "B16") (pin "P$3") (pinfunction "K2_P$3") (pintype "bidirectional"))
      (node (ref "R24") (pin "1") (pinfunction "1_1") (pintype "passive"))
    )
    (net (code "79") (name "L32") (class "Default")
      (node (ref "B17") (pin "P$2") (pinfunction "K1_P$2") (pintype "bidirectional"))
      (node (ref "B17ALT") (pin "P$2") (pinfunction "K1_P$2") (pintype "bidirectional"))
      (node (ref "R55") (pin "1") (pinfunction "1_1") (pintype "passive"))
    )
    (net (code "80") (name "L33") (class "Default")
      (node (ref "B17") (pin "P$3") (pinfunction "K2_P$3") (pintype "bidirectional"))
      (node (ref "B17ALT") (pin "P$3") (pinfunction "K2_P$3") (pintype "bidirectional"))
      (node (ref "R54") (pin "1") (pinfunction "1_1") (pintype "passive"))
    )
    (net (code "81") (name "L34") (class "Default")
      (node (ref "B18") (pin "P$2") (pinfunction "K1_P$2") (pintype "bidirectional"))
      (node (ref "R53") (pin "1") (pinfunction "1_1") (pintype "passive"))
    )
    (net (code "82") (name "L35") (class "Default")
      (node (ref "B18") (pin "P$3") (pinfunction "K2_P$3") (pintype "bidirectional"))
      (node (ref "R52") (pin "1") (pinfunction "1_1") (pintype "passive"))
    )
    (net (code "83") (name "L36") (class "Default")
      (node (ref "B19") (pin "P$2") (pinfunction "K1_P$2") (pintype "bidirectional"))
      (node (ref "R51") (pin "1") (pinfunction "1_1") (pintype "passive"))
    )
    (net (code "84") (name "L37") (class "Default")
      (node (ref "B19") (pin "P$3") (pinfunction "K2_P$3") (pintype "bidirectional"))
      (node (ref "R50") (pin "1") (pinfunction "1_1") (pintype "passive"))
    )
    (net (code "85") (name "L38") (class "Default")
      (node (ref "B20") (pin "P$2") (pinfunction "K1_P$2") (pintype "bidirectional"))
      (node (ref "B20ALT") (pin "P$2") (pinfunction "K1_P$2") (pintype "bidirectional"))
      (node (ref "R49") (pin "1") (pinfunction "1_1") (pintype "passive"))
    )
    (net (code "86") (name "L39") (class "Default")
      (node (ref "B20") (pin "P$3") (pinfunction "K2_P$3") (pintype "bidirectional"))
      (node (ref "B20ALT") (pin "P$3") (pinfunction "K2_P$3") (pintype "bidirectional"))
      (node (ref "R48") (pin "1") (pinfunction "1_1") (pintype "passive"))
    )
    (net (code "87") (name "L40") (class "Default")
      (node (ref "B21") (pin "P$2") (pinfunction "K1_P$2") (pintype "bidirectional"))
      (node (ref "B21ALT") (pin "P$2") (pinfunction "K1_P$2") (pintype "bidirectional"))
      (node (ref "R47") (pin "1") (pinfunction "1_1") (pintype "passive"))
    )
    (net (code "88") (name "L41") (class "Default")
      (node (ref "B21") (pin "P$3") (pinfunction "K2_P$3") (pintype "bidirectional"))
      (node (ref "B21ALT") (pin "P$3") (pinfunction "K2_P$3") (pintype "bidirectional"))
      (node (ref "R46") (pin "1") (pinfunction "1_1") (pintype "passive"))
    )
    (net (code "89") (name "L42") (class "Default")
      (node (ref "B22") (pin "P$2") (pinfunction "K1_P$2") (pintype "bidirectional"))
      (node (ref "R45") (pin "1") (pinfunction "1_1") (pintype "passive"))
    )
    (net (code "90") (name "L43") (class "Default")
      (node (ref "B22") (pin "P$3") (pinfunction "K2_P$3") (pintype "bidirectional"))
      (node (ref "R44") (pin "1") (pinfunction "1_1") (pintype "passive"))
    )
    (net (code "91") (name "L44") (class "Default")
      (node (ref "B23") (pin "P$2") (pinfunction "K1_P$2") (pintype "bidirectional"))
      (node (ref "R43") (pin "1") (pinfunction "1_1") (pintype "passive"))
    )
    (net (code "92") (name "L45") (class "Default")
      (node (ref "B23") (pin "P$3") (pinfunction "K2_P$3") (pintype "bidirectional"))
      (node (ref "R42") (pin "1") (pinfunction "1_1") (pintype "passive"))
    )
    (net (code "93") (name "L46") (class "Default")
      (node (ref "B24") (pin "P$2") (pinfunction "K1_P$2") (pintype "bidirectional"))
      (node (ref "R41") (pin "1") (pinfunction "1_1") (pintype "passive"))
    )
    (net (code "94") (name "L47") (class "Default")
      (node (ref "B24") (pin "P$3") (pinfunction "K2_P$3") (pintype "bidirectional"))
      (node (ref "R40") (pin "1") (pinfunction "1_1") (pintype "passive"))
    )
    (net (code "95") (name "L48") (class "Default")
      (node (ref "B25") (pin "P$2") (pinfunction "K1_P$2") (pintype "bidirectional"))
      (node (ref "R71") (pin "1") (pinfunction "1_1") (pintype "passive"))
    )
    (net (code "96") (name "L49") (class "Default")
      (node (ref "B25") (pin "P$3") (pinfunction "K2_P$3") (pintype "bidirectional"))
      (node (ref "R70") (pin "1") (pinfunction "1_1") (pintype "passive"))
    )
    (net (code "97") (name "L50") (class "Default")
      (node (ref "B26") (pin "P$2") (pinfunction "K1_P$2") (pintype "bidirectional"))
      (node (ref "B26ALT") (pin "P$2") (pinfunction "K1_P$2") (pintype "bidirectional"))
      (node (ref "R69") (pin "1") (pinfunction "1_1") (pintype "passive"))
    )
    (net (code "98") (name "L51") (class "Default")
      (node (ref "B26") (pin "P$3") (pinfunction "K2_P$3") (pintype "bidirectional"))
      (node (ref "B26ALT") (pin "P$3") (pinfunction "K2_P$3") (pintype "bidirectional"))
      (node (ref "R68") (pin "1") (pinfunction "1_1") (pintype "passive"))
    )
    (net (code "99") (name "L52") (class "Default")
      (node (ref "B27") (pin "P$2") (pinfunction "K1_P$2") (pintype "bidirectional"))
      (node (ref "B27ALT") (pin "P$2") (pinfunction "K1_P$2") (pintype "bidirectional"))
      (node (ref "R67") (pin "1") (pinfunction "1_1") (pintype "passive"))
    )
    (net (code "100") (name "L53") (class "Default")
      (node (ref "B27") (pin "P$3") (pinfunction "K2_P$3") (pintype "bidirectional"))
      (node (ref "B27ALT") (pin "P$3") (pinfunction "K2_P$3") (pintype "bidirectional"))
      (node (ref "R66") (pin "1") (pinfunction "1_1") (pintype "passive"))
    )
    (net (code "101") (name "L54") (class "Default")
      (node (ref "B28") (pin "P$2") (pinfunction "K1_P$2") (pintype "bidirectional"))
      (node (ref "R65") (pin "1") (pinfunction "1_1") (pintype "passive"))
    )
    (net (code "102") (name "L55") (class "Default")
      (node (ref "B28") (pin "P$3") (pinfunction "K2_P$3") (pintype "bidirectional"))
      (node (ref "R64") (pin "1") (pinfunction "1_1") (pintype "passive"))
    )
    (net (code "103") (name "L56") (class "Default")
      (node (ref "B29") (pin "P$2") (pinfunction "K1_P$2") (pintype "bidirectional"))
      (node (ref "R63") (pin "1") (pinfunction "1_1") (pintype "passive"))
    )
    (net (code "104") (name "L57") (class "Default")
      (node (ref "B29") (pin "P$3") (pinfunction "K2_P$3") (pintype "bidirectional"))
      (node (ref "R62") (pin "1") (pinfunction "1_1") (pintype "passive"))
    )
    (net (code "105") (name "L58") (class "Default")
      (node (ref "B30") (pin "P$2") (pinfunction "K1_P$2") (pintype "bidirectional"))
      (node (ref "R61") (pin "1") (pinfunction "1_1") (pintype "passive"))
    )
    (net (code "106") (name "L59") (class "Default")
      (node (ref "B30") (pin "P$3") (pinfunction "K2_P$3") (pintype "bidirectional"))
      (node (ref "R60") (pin "1") (pinfunction "1_1") (pintype "passive"))
    )
    (net (code "107") (name "MOSI") (class "Default")
      (node (ref "SERIAL2") (pin "8") (pinfunction "8_8") (pintype "passive"))
      (node (ref "SSW1") (pin "6") (pinfunction "SDI_6") (pintype "bidirectional"))
      (node (ref "SSW2") (pin "6") (pinfunction "SDI_6") (pintype "bidirectional"))
    )
    (net (code "108") (name "Net-(IC2-L0)") (class "Default")
      (node (ref "IC2") (pin "6") (pinfunction "L0_6") (pintype "output"))
      (node (ref "R23") (pin "2") (pinfunction "2_2") (pintype "passive"))
    )
    (net (code "109") (name "Net-(IC2-L1)") (class "Default")
      (node (ref "IC2") (pin "7") (pinfunction "L1_7") (pintype "output"))
      (node (ref "R22") (pin "2") (pinfunction "2_2") (pintype "passive"))
    )
    (net (code "110") (name "Net-(IC2-L2)") (class "Default")
      (node (ref "IC2") (pin "8") (pinfunction "L2_8") (pintype "output"))
      (node (ref "R21") (pin "2") (pinfunction "2_2") (pintype "passive"))
    )
    (net (code "111") (name "Net-(IC2-L3)") (class "Default")
      (node (ref "IC2") (pin "9") (pinfunction "L3_9") (pintype "output"))
      (node (ref "R20") (pin "2") (pinfunction "2_2") (pintype "passive"))
    )
    (net (code "112") (name "Net-(IC2-L4)") (class "Default")
      (node (ref "IC2") (pin "10") (pinfunction "L4_10") (pintype "output"))
      (node (ref "R19") (pin "2") (pinfunction "2_2") (pintype "passive"))
    )
    (net (code "113") (name "Net-(IC2-L5)") (class "Default")
      (node (ref "IC2") (pin "11") (pinfunction "L5_11") (pintype "output"))
      (node (ref "R18") (pin "2") (pinfunction "2_2") (pintype "passive"))
    )
    (net (code "114") (name "Net-(IC2-L6)") (class "Default")
      (node (ref "IC2") (pin "12") (pinfunction "L6_12") (pintype "output"))
      (node (ref "R17") (pin "2") (pinfunction "2_2") (pintype "passive"))
    )
    (net (code "115") (name "Net-(IC2-L7)") (class "Default")
      (node (ref "IC2") (pin "13") (pinfunction "L7_13") (pintype "output"))
      (node (ref "R16") (pin "2") (pinfunction "2_2") (pintype "passive"))
    )
    (net (code "116") (name "Net-(IC2-L8)") (class "Default")
      (node (ref "IC2") (pin "15") (pinfunction "L8_15") (pintype "output"))
      (node (ref "R15") (pin "2") (pinfunction "2_2") (pintype "passive"))
    )
    (net (code "117") (name "Net-(IC2-L9)") (class "Default")
      (node (ref "IC2") (pin "16") (pinfunction "L9_16") (pintype "output"))
      (node (ref "R14") (pin "2") (pinfunction "2_2") (pintype "passive"))
    )
    (net (code "118") (name "Net-(IC2-L10)") (class "Default")
      (node (ref "IC2") (pin "17") (pinfunction "L10_17") (pintype "output"))
      (node (ref "R13") (pin "2") (pinfunction "2_2") (pintype "passive"))
    )
    (net (code "119") (name "Net-(IC2-L11)") (class "Default")
      (node (ref "IC2") (pin "18") (pinfunction "L11_18") (pintype "output"))
      (node (ref "R12") (pin "2") (pinfunction "2_2") (pintype "passive"))
    )
    (net (code "120") (name "Net-(IC2-L12)") (class "Default")
      (node (ref "IC2") (pin "19") (pinfunction "L12_19") (pintype "output"))
      (node (ref "R11") (pin "2") (pinfunction "2_2") (pintype "passive"))
    )
    (net (code "121") (name "Net-(IC2-L13)") (class "Default")
      (node (ref "IC2") (pin "20") (pinfunction "L13_20") (pintype "output"))
      (node (ref "R10") (pin "2") (pinfunction "2_2") (pintype "passive"))
    )
    (net (code "122") (name "Net-(IC2-L14)") (class "Default")
      (node (ref "IC2") (pin "21") (pinfunction "L14_21") (pintype "output"))
      (node (ref "R4") (pin "2") (pinfunction "2_2") (pintype "passive"))
    )
    (net (code "123") (name "Net-(IC2-L15)") (class "Default")
      (node (ref "IC2") (pin "22") (pinfunction "L15_22") (pintype "output"))
      (node (ref "R3") (pin "2") (pinfunction "2_2") (pintype "passive"))
    )
    (net (code "124") (name "Net-(IC3-L0)") (class "Default")
      (node (ref "IC3") (pin "6") (pinfunction "L0_6") (pintype "output"))
      (node (ref "R39") (pin "2") (pinfunction "2_2") (pintype "passive"))
    )
    (net (code "125") (name "Net-(IC3-L1)") (class "Default")
      (node (ref "IC3") (pin "7") (pinfunction "L1_7") (pintype "output"))
      (node (ref "R38") (pin "2") (pinfunction "2_2") (pintype "passive"))
    )
    (net (code "126") (name "Net-(IC3-L2)") (class "Default")
      (node (ref "IC3") (pin "8") (pinfunction "L2_8") (pintype "output"))
      (node (ref "R37") (pin "2") (pinfunction "2_2") (pintype "passive"))
    )
    (net (code "127") (name "Net-(IC3-L3)") (class "Default")
      (node (ref "IC3") (pin "9") (pinfunction "L3_9") (pintype "output"))
      (node (ref "R36") (pin "2") (pinfunction "2_2") (pintype "passive"))
    )
    (net (code "128") (name "Net-(IC3-L4)") (class "Default")
      (node (ref "IC3") (pin "10") (pinfunction "L4_10") (pintype "output"))
      (node (ref "R35") (pin "2") (pinfunction "2_2") (pintype "passive"))
    )
    (net (code "129") (name "Net-(IC3-L5)") (class "Default")
      (node (ref "IC3") (pin "11") (pinfunction "L5_11") (pintype "output"))
      (node (ref "R34") (pin "2") (pinfunction "2_2") (pintype "passive"))
    )
    (net (code "130") (name "Net-(IC3-L6)") (class "Default")
      (node (ref "IC3") (pin "12") (pinfunction "L6_12") (pintype "output"))
      (node (ref "R33") (pin "2") (pinfunction "2_2") (pintype "passive"))
    )
    (net (code "131") (name "Net-(IC3-L7)") (class "Default")
      (node (ref "IC3") (pin "13") (pinfunction "L7_13") (pintype "output"))
      (node (ref "R32") (pin "2") (pinfunction "2_2") (pintype "passive"))
    )
    (net (code "132") (name "Net-(IC3-L8)") (class "Default")
      (node (ref "IC3") (pin "15") (pinfunction "L8_15") (pintype "output"))
      (node (ref "R31") (pin "2") (pinfunction "2_2") (pintype "passive"))
    )
    (net (code "133") (name "Net-(IC3-L9)") (class "Default")
      (node (ref "IC3") (pin "16") (pinfunction "L9_16") (pintype "output"))
      (node (ref "R30") (pin "2") (pinfunction "2_2") (pintype "passive"))
    )
    (net (code "134") (name "Net-(IC3-L10)") (class "Default")
      (node (ref "IC3") (pin "17") (pinfunction "L10_17") (pintype "output"))
      (node (ref "R29") (pin "2") (pinfunction "2_2") (pintype "passive"))
    )
    (net (code "135") (name "Net-(IC3-L11)") (class "Default")
      (node (ref "IC3") (pin "18") (pinfunction "L11_18") (pintype "output"))
      (node (ref "R28") (pin "2") (pinfunction "2_2") (pintype "passive"))
    )
    (net (code "136") (name "Net-(IC3-L12)") (class "Default")
      (node (ref "IC3") (pin "19") (pinfunction "L12_19") (pintype "output"))
      (node (ref "R27") (pin "2") (pinfunction "2_2") (pintype "passive"))
    )
    (net (code "137") (name "Net-(IC3-L13)") (class "Default")
      (node (ref "IC3") (pin "20") (pinfunction "L13_20") (pintype "output"))
      (node (ref "R26") (pin "2") (pinfunction "2_2") (pintype "passive"))
    )
    (net (code "138") (name "Net-(IC3-L14)") (class "Default")
      (node (ref "IC3") (pin "21") (pinfunction "L14_21") (pintype "output"))
      (node (ref "R25") (pin "2") (pinfunction "2_2") (pintype "passive"))
    )
    (net (code "139") (name "Net-(IC3-L15)") (class "Default")
      (node (ref "IC3") (pin "22") (pinfunction "L15_22") (pintype "output"))
      (node (ref "R24") (pin "2") (pinfunction "2_2") (pintype "passive"))
    )
    (net (code "140") (name "Net-(IC4-L0)") (class "Default")
      (node (ref "IC4") (pin "6") (pinfunction "L0_6") (pintype "output"))
      (node (ref "R55") (pin "2") (pinfunction "2_2") (pintype "passive"))
    )
    (net (code "141") (name "Net-(IC4-L1)") (class "Default")
      (node (ref "IC4") (pin "7") (pinfunction "L1_7") (pintype "output"))
      (node (ref "R54") (pin "2") (pinfunction "2_2") (pintype "passive"))
    )
    (net (code "142") (name "Net-(IC4-L2)") (class "Default")
      (node (ref "IC4") (pin "8") (pinfunction "L2_8") (pintype "output"))
      (node (ref "R53") (pin "2") (pinfunction "2_2") (pintype "passive"))
    )
    (net (code "143") (name "Net-(IC4-L3)") (class "Default")
      (node (ref "IC4") (pin "9") (pinfunction "L3_9") (pintype "output"))
      (node (ref "R52") (pin "2") (pinfunction "2_2") (pintype "passive"))
    )
    (net (code "144") (name "Net-(IC4-L4)") (class "Default")
      (node (ref "IC4") (pin "10") (pinfunction "L4_10") (pintype "output"))
      (node (ref "R51") (pin "2") (pinfunction "2_2") (pintype "passive"))
    )
    (net (code "145") (name "Net-(IC4-L5)") (class "Default")
      (node (ref "IC4") (pin "11") (pinfunction "L5_11") (pintype "output"))
      (node (ref "R50") (pin "2") (pinfunction "2_2") (pintype "passive"))
    )
    (net (code "146") (name "Net-(IC4-L6)") (class "Default")
      (node (ref "IC4") (pin "12") (pinfunction "L6_12") (pintype "output"))
      (node (ref "R49") (pin "2") (pinfunction "2_2") (pintype "passive"))
    )
    (net (code "147") (name "Net-(IC4-L7)") (class "Default")
      (node (ref "IC4") (pin "13") (pinfunction "L7_13") (pintype "output"))
      (node (ref "R48") (pin "2") (pinfunction "2_2") (pintype "passive"))
    )
    (net (code "148") (name "Net-(IC4-L8)") (class "Default")
      (node (ref "IC4") (pin "15") (pinfunction "L8_15") (pintype "output"))
      (node (ref "R47") (pin "2") (pinfunction "2_2") (pintype "passive"))
    )
    (net (code "149") (name "Net-(IC4-L9)") (class "Default")
      (node (ref "IC4") (pin "16") (pinfunction "L9_16") (pintype "output"))
      (node (ref "R46") (pin "2") (pinfunction "2_2") (pintype "passive"))
    )
    (net (code "150") (name "Net-(IC4-L10)") (class "Default")
      (node (ref "IC4") (pin "17") (pinfunction "L10_17") (pintype "output"))
      (node (ref "R45") (pin "2") (pinfunction "2_2") (pintype "passive"))
    )
    (net (code "151") (name "Net-(IC4-L11)") (class "Default")
      (node (ref "IC4") (pin "18") (pinfunction "L11_18") (pintype "output"))
      (node (ref "R44") (pin "2") (pinfunction "2_2") (pintype "passive"))
    )
    (net (code "152") (name "Net-(IC4-L12)") (class "Default")
      (node (ref "IC4") (pin "19") (pinfunction "L12_19") (pintype "output"))
      (node (ref "R43") (pin "2") (pinfunction "2_2") (pintype "passive"))
    )
    (net (code "153") (name "Net-(IC4-L13)") (class "Default")
      (node (ref "IC4") (pin "20") (pinfunction "L13_20") (pintype "output"))
      (node (ref "R42") (pin "2") (pinfunction "2_2") (pintype "passive"))
    )
    (net (code "154") (name "Net-(IC4-L14)") (class "Default")
      (node (ref "IC4") (pin "21") (pinfunction "L14_21") (pintype "output"))
      (node (ref "R41") (pin "2") (pinfunction "2_2") (pintype "passive"))
    )
    (net (code "155") (name "Net-(IC4-L15)") (class "Default")
      (node (ref "IC4") (pin "22") (pinfunction "L15_22") (pintype "output"))
      (node (ref "R40") (pin "2") (pinfunction "2_2") (pintype "passive"))
    )
    (net (code "156") (name "Net-(IC5-L0)") (class "Default")
      (node (ref "IC5") (pin "6") (pinfunction "L0_6") (pintype "output"))
      (node (ref "R71") (pin "2") (pinfunction "2_2") (pintype "passive"))
    )
    (net (code "157") (name "Net-(IC5-L1)") (class "Default")
      (node (ref "IC5") (pin "7") (pinfunction "L1_7") (pintype "output"))
      (node (ref "R70") (pin "2") (pinfunction "2_2") (pintype "passive"))
    )
    (net (code "158") (name "Net-(IC5-L2)") (class "Default")
      (node (ref "IC5") (pin "8") (pinfunction "L2_8") (pintype "output"))
      (node (ref "R69") (pin "2") (pinfunction "2_2") (pintype "passive"))
    )
    (net (code "159") (name "Net-(IC5-L3)") (class "Default")
      (node (ref "IC5") (pin "9") (pinfunction "L3_9") (pintype "output"))
      (node (ref "R68") (pin "2") (pinfunction "2_2") (pintype "passive"))
    )
    (net (code "160") (name "Net-(IC5-L4)") (class "Default")
      (node (ref "IC5") (pin "10") (pinfunction "L4_10") (pintype "output"))
      (node (ref "R67") (pin "2") (pinfunction "2_2") (pintype "passive"))
    )
    (net (code "161") (name "Net-(IC5-L5)") (class "Default")
      (node (ref "IC5") (pin "11") (pinfunction "L5_11") (pintype "output"))
      (node (ref "R66") (pin "2") (pinfunction "2_2") (pintype "passive"))
    )
    (net (code "162") (name "Net-(IC5-L6)") (class "Default")
      (node (ref "IC5") (pin "12") (pinfunction "L6_12") (pintype "output"))
      (node (ref "R65") (pin "2") (pinfunction "2_2") (pintype "passive"))
    )
    (net (code "163") (name "Net-(IC5-L7)") (class "Default")
      (node (ref "IC5") (pin "13") (pinfunction "L7_13") (pintype "output"))
      (node (ref "R64") (pin "2") (pinfunction "2_2") (pintype "passive"))
    )
    (net (code "164") (name "Net-(IC5-L8)") (class "Default")
      (node (ref "IC5") (pin "15") (pinfunction "L8_15") (pintype "output"))
      (node (ref "R63") (pin "2") (pinfunction "2_2") (pintype "passive"))
    )
    (net (code "165") (name "Net-(IC5-L9)") (class "Default")
      (node (ref "IC5") (pin "16") (pinfunction "L9_16") (pintype "output"))
      (node (ref "R62") (pin "2") (pinfunction "2_2") (pintype "passive"))
    )
    (net (code "166") (name "Net-(IC5-L10)") (class "Default")
      (node (ref "IC5") (pin "17") (pinfunction "L10_17") (pintype "output"))
      (node (ref "R61") (pin "2") (pinfunction "2_2") (pintype "passive"))
    )
    (net (code "167") (name "Net-(IC5-L11)") (class "Default")
      (node (ref "IC5") (pin "18") (pinfunction "L11_18") (pintype "output"))
      (node (ref "R60") (pin "2") (pinfunction "2_2") (pintype "passive"))
    )
    (net (code "168") (name "Net-(IC9A-I)") (class "Default")
      (node (ref "C24") (pin "1") (pinfunction "1_1") (pintype "passive"))
      (node (ref "IC9") (pin "13") (pinfunction "I_13") (pintype "input"))
      (node (ref "R56") (pin "1") (pinfunction "1_1") (pintype "passive"))
    )
    (net (code "169") (name "Net-(L2-Pad1)") (class "Default")
      (node (ref "L2") (pin "1") (pinfunction "1_1") (pintype "passive"))
      (node (ref "SERIAL2") (pin "2") (pinfunction "2_2") (pintype "passive"))
    )
    (net (code "170") (name "Net-(R56-Pad2)") (class "Default")
      (node (ref "R56") (pin "2") (pinfunction "2_2") (pintype "passive"))
      (node (ref "R58") (pin "1") (pinfunction "1_1") (pintype "passive"))
      (node (ref "SW1") (pin "B") (pinfunction "B_B") (pintype "passive"))
      (node (ref "U$66") (pin "2") (pinfunction "2_2") (pintype "passive"))
    )
    (net (code "171") (name "SCLK") (class "Default")
      (node (ref "SERIAL2") (pin "7") (pinfunction "7_7") (pintype "passive"))
      (node (ref "SSW1") (pin "7") (pinfunction "SCK_7") (pintype "bidirectional"))
      (node (ref "SSW2") (pin "7") (pinfunction "SCK_7") (pintype "bidirectional"))
    )
    (net (code "172") (name "unconnected-(IC1-INTA-Pad20)") (class "Default")
      (node (ref "IC1") (pin "20") (pinfunction "INTA_20") (pintype "output"))
    )
    (net (code "173") (name "unconnected-(IC1-INTB-Pad19)") (class "Default")
      (node (ref "IC1") (pin "19") (pinfunction "INTB_19") (pintype "output"))
    )
    (net (code "174") (name "unconnected-(IC5-L12-Pad19)") (class "Default")
      (node (ref "IC5") (pin "19") (pinfunction "L12_19") (pintype "output"))
    )
    (net (code "175") (name "unconnected-(IC5-L13-Pad20)") (class "Default")
      (node (ref "IC5") (pin "20") (pinfunction "L13_20") (pintype "output"))
    )
    (net (code "176") (name "unconnected-(IC5-L14-Pad21)") (class "Default")
      (node (ref "IC5") (pin "21") (pinfunction "L14_21") (pintype "output"))
    )
    (net (code "177") (name "unconnected-(IC5-L15-Pad22)") (class "Default")
      (node (ref "IC5") (pin "22") (pinfunction "L15_22") (pintype "output"))
    )
    (net (code "178") (name "unconnected-(IC6-INTA-Pad20)") (class "Default")
      (node (ref "IC6") (pin "20") (pinfunction "INTA_20") (pintype "output"))
    )
    (net (code "179") (name "unconnected-(IC6-INTB-Pad19)") (class "Default")
      (node (ref "IC6") (pin "19") (pinfunction "INTB_19") (pintype "output"))
    )
    (net (code "180") (name "unconnected-(IC7-GPA2-Pad23)") (class "Default")
      (node (ref "IC7") (pin "23") (pinfunction "GPA2_23") (pintype "bidirectional"))
    )
    (net (code "181") (name "unconnected-(IC7-GPA3-Pad24)") (class "Default")
      (node (ref "IC7") (pin "24") (pinfunction "GPA3_24") (pintype "bidirectional"))
    )
    (net (code "182") (name "unconnected-(IC7-GPA4-Pad25)") (class "Default")
      (node (ref "IC7") (pin "25") (pinfunction "GPA4_25") (pintype "bidirectional"))
    )
    (net (code "183") (name "unconnected-(IC7-GPA5-Pad26)") (class "Default")
      (node (ref "IC7") (pin "26") (pinfunction "GPA5_26") (pintype "bidirectional"))
    )
    (net (code "184") (name "unconnected-(IC7-GPA6-Pad27)") (class "Default")
      (node (ref "IC7") (pin "27") (pinfunction "GPA6_27") (pintype "bidirectional"))
    )
    (net (code "185") (name "unconnected-(IC7-GPA7-Pad28)") (class "Default")
      (node (ref "IC7") (pin "28") (pinfunction "GPA7_28") (pintype "bidirectional"))
    )
    (net (code "186") (name "unconnected-(IC7-GPB2-Pad3)") (class "Default")
      (node (ref "IC7") (pin "3") (pinfunction "GPB2_3") (pintype "bidirectional"))
    )
    (net (code "187") (name "unconnected-(IC7-GPB3-Pad4)") (class "Default")
      (node (ref "IC7") (pin "4") (pinfunction "GPB3_4") (pintype "bidirectional"))
    )
    (net (code "188") (name "unconnected-(IC7-GPB4-Pad5)") (class "Default")
      (node (ref "IC7") (pin "5") (pinfunction "GPB4_5") (pintype "bidirectional"))
    )
    (net (code "189") (name "unconnected-(IC7-GPB5-Pad6)") (class "Default")
      (node (ref "IC7") (pin "6") (pinfunction "GPB5_6") (pintype "bidirectional"))
    )
    (net (code "190") (name "unconnected-(IC7-GPB6-Pad7)") (class "Default")
      (node (ref "IC7") (pin "7") (pinfunction "GPB6_7") (pintype "bidirectional"))
    )
    (net (code "191") (name "unconnected-(IC7-GPB7-Pad8)") (class "Default")
      (node (ref "IC7") (pin "8") (pinfunction "GPB7_8") (pintype "bidirectional"))
    )
    (net (code "192") (name "unconnected-(IC7-INTA-Pad20)") (class "Default")
      (node (ref "IC7") (pin "20") (pinfunction "INTA_20") (pintype "output"))
    )
    (net (code "193") (name "unconnected-(IC7-INTB-Pad19)") (class "Default")
      (node (ref "IC7") (pin "19") (pinfunction "INTB_19") (pintype "output"))
    )
    (net (code "194") (name "unconnected-(IC8-GPA2-Pad23)") (class "Default")
      (node (ref "IC8") (pin "23") (pinfunction "GPA2_23") (pintype "bidirectional"))
    )
    (net (code "195") (name "unconnected-(IC8-GPA3-Pad24)") (class "Default")
      (node (ref "IC8") (pin "24") (pinfunction "GPA3_24") (pintype "bidirectional"))
    )
    (net (code "196") (name "unconnected-(IC8-GPA4-Pad25)") (class "Default")
      (node (ref "IC8") (pin "25") (pinfunction "GPA4_25") (pintype "bidirectional"))
    )
    (net (code "197") (name "unconnected-(IC8-GPA5-Pad26)") (class "Default")
      (node (ref "IC8") (pin "26") (pinfunction "GPA5_26") (pintype "bidirectional"))
    )
    (net (code "198") (name "unconnected-(IC8-GPA6-Pad27)") (class "Default")
      (node (ref "IC8") (pin "27") (pinfunction "GPA6_27") (pintype "bidirectional"))
    )
    (net (code "199") (name "unconnected-(IC8-GPA7-Pad28)") (class "Default")
      (node (ref "IC8") (pin "28") (pinfunction "GPA7_28") (pintype "bidirectional"))
    )
    (net (code "200") (name "unconnected-(IC8-GPB1-Pad2)") (class "Default")
      (node (ref "IC8") (pin "2") (pinfunction "GPB1_2") (pintype "bidirectional"))
    )
    (net (code "201") (name "unconnected-(IC8-GPB2-Pad3)") (class "Default")
      (node (ref "IC8") (pin "3") (pinfunction "GPB2_3") (pintype "bidirectional"))
    )
    (net (code "202") (name "unconnected-(IC8-GPB3-Pad4)") (class "Default")
      (node (ref "IC8") (pin "4") (pinfunction "GPB3_4") (pintype "bidirectional"))
    )
    (net (code "203") (name "unconnected-(IC8-GPB4-Pad5)") (class "Default")
      (node (ref "IC8") (pin "5") (pinfunction "GPB4_5") (pintype "bidirectional"))
    )
    (net (code "204") (name "unconnected-(IC8-GPB5-Pad6)") (class "Default")
      (node (ref "IC8") (pin "6") (pinfunction "GPB5_6") (pintype "bidirectional"))
    )
    (net (code "205") (name "unconnected-(IC8-GPB6-Pad7)") (class "Default")
      (node (ref "IC8") (pin "7") (pinfunction "GPB6_7") (pintype "bidirectional"))
    )
    (net (code "206") (name "unconnected-(IC8-GPB7-Pad8)") (class "Default")
      (node (ref "IC8") (pin "8") (pinfunction "GPB7_8") (pintype "bidirectional"))
    )
    (net (code "207") (name "unconnected-(IC8-INTA-Pad20)") (class "Default")
      (node (ref "IC8") (pin "20") (pinfunction "INTA_20") (pintype "output"))
    )
    (net (code "208") (name "unconnected-(IC8-INTB-Pad19)") (class "Default")
      (node (ref "IC8") (pin "19") (pinfunction "INTB_19") (pintype "output"))
    )
    (net (code "209") (name "unconnected-(IC9B-O-Pad10)") (class "Default")
      (node (ref "IC9") (pin "10") (pinfunction "O_10") (pintype "output"))
    )
    (net (code "210") (name "unconnected-(IC9C-O-Pad8)") (class "Default")
      (node (ref "IC9") (pin "8") (pinfunction "O_8") (pintype "output"))
    )
    (net (code "211") (name "unconnected-(IC9D-O-Pad2)") (class "Default")
      (node (ref "IC9") (pin "2") (pinfunction "O_2") (pintype "output"))
    )
    (net (code "212") (name "unconnected-(IC9E-O-Pad4)") (class "Default")
      (node (ref "IC9") (pin "4") (pinfunction "O_4") (pintype "output"))
    )
    (net (code "213") (name "unconnected-(IC9F-O-Pad6)") (class "Default")
      (node (ref "IC9") (pin "6") (pinfunction "O_6") (pintype "output"))
    )
    (net (code "214") (name "unconnected-(SERIAL2-Pad6)") (class "Default")
      (node (ref "SERIAL2") (pin "6") (pinfunction "6_6") (pintype "passive"))
    )
    (net (code "215") (name "unconnected-(SSW1-SDO-Pad5)") (class "Default")
      (node (ref "SSW1") (pin "5") (pinfunction "SDO_5") (pintype "bidirectional"))
    )
    (net (code "216") (name "unconnected-(SSW2-SDO-Pad5)") (class "Default")
      (node (ref "SSW2") (pin "5") (pinfunction "SDO_5") (pintype "bidirectional"))
    )
    (net (code "217") (name "unconnected-(U$34-PadA1)") (class "Default")
      (node (ref "U$34") (pin "A1") (pinfunction "A1_A1") (pintype "passive"))
    )
  )
)
